# FPGA_SDRAM.net
KiCad netlist of a schematic drawn in Altium Designer
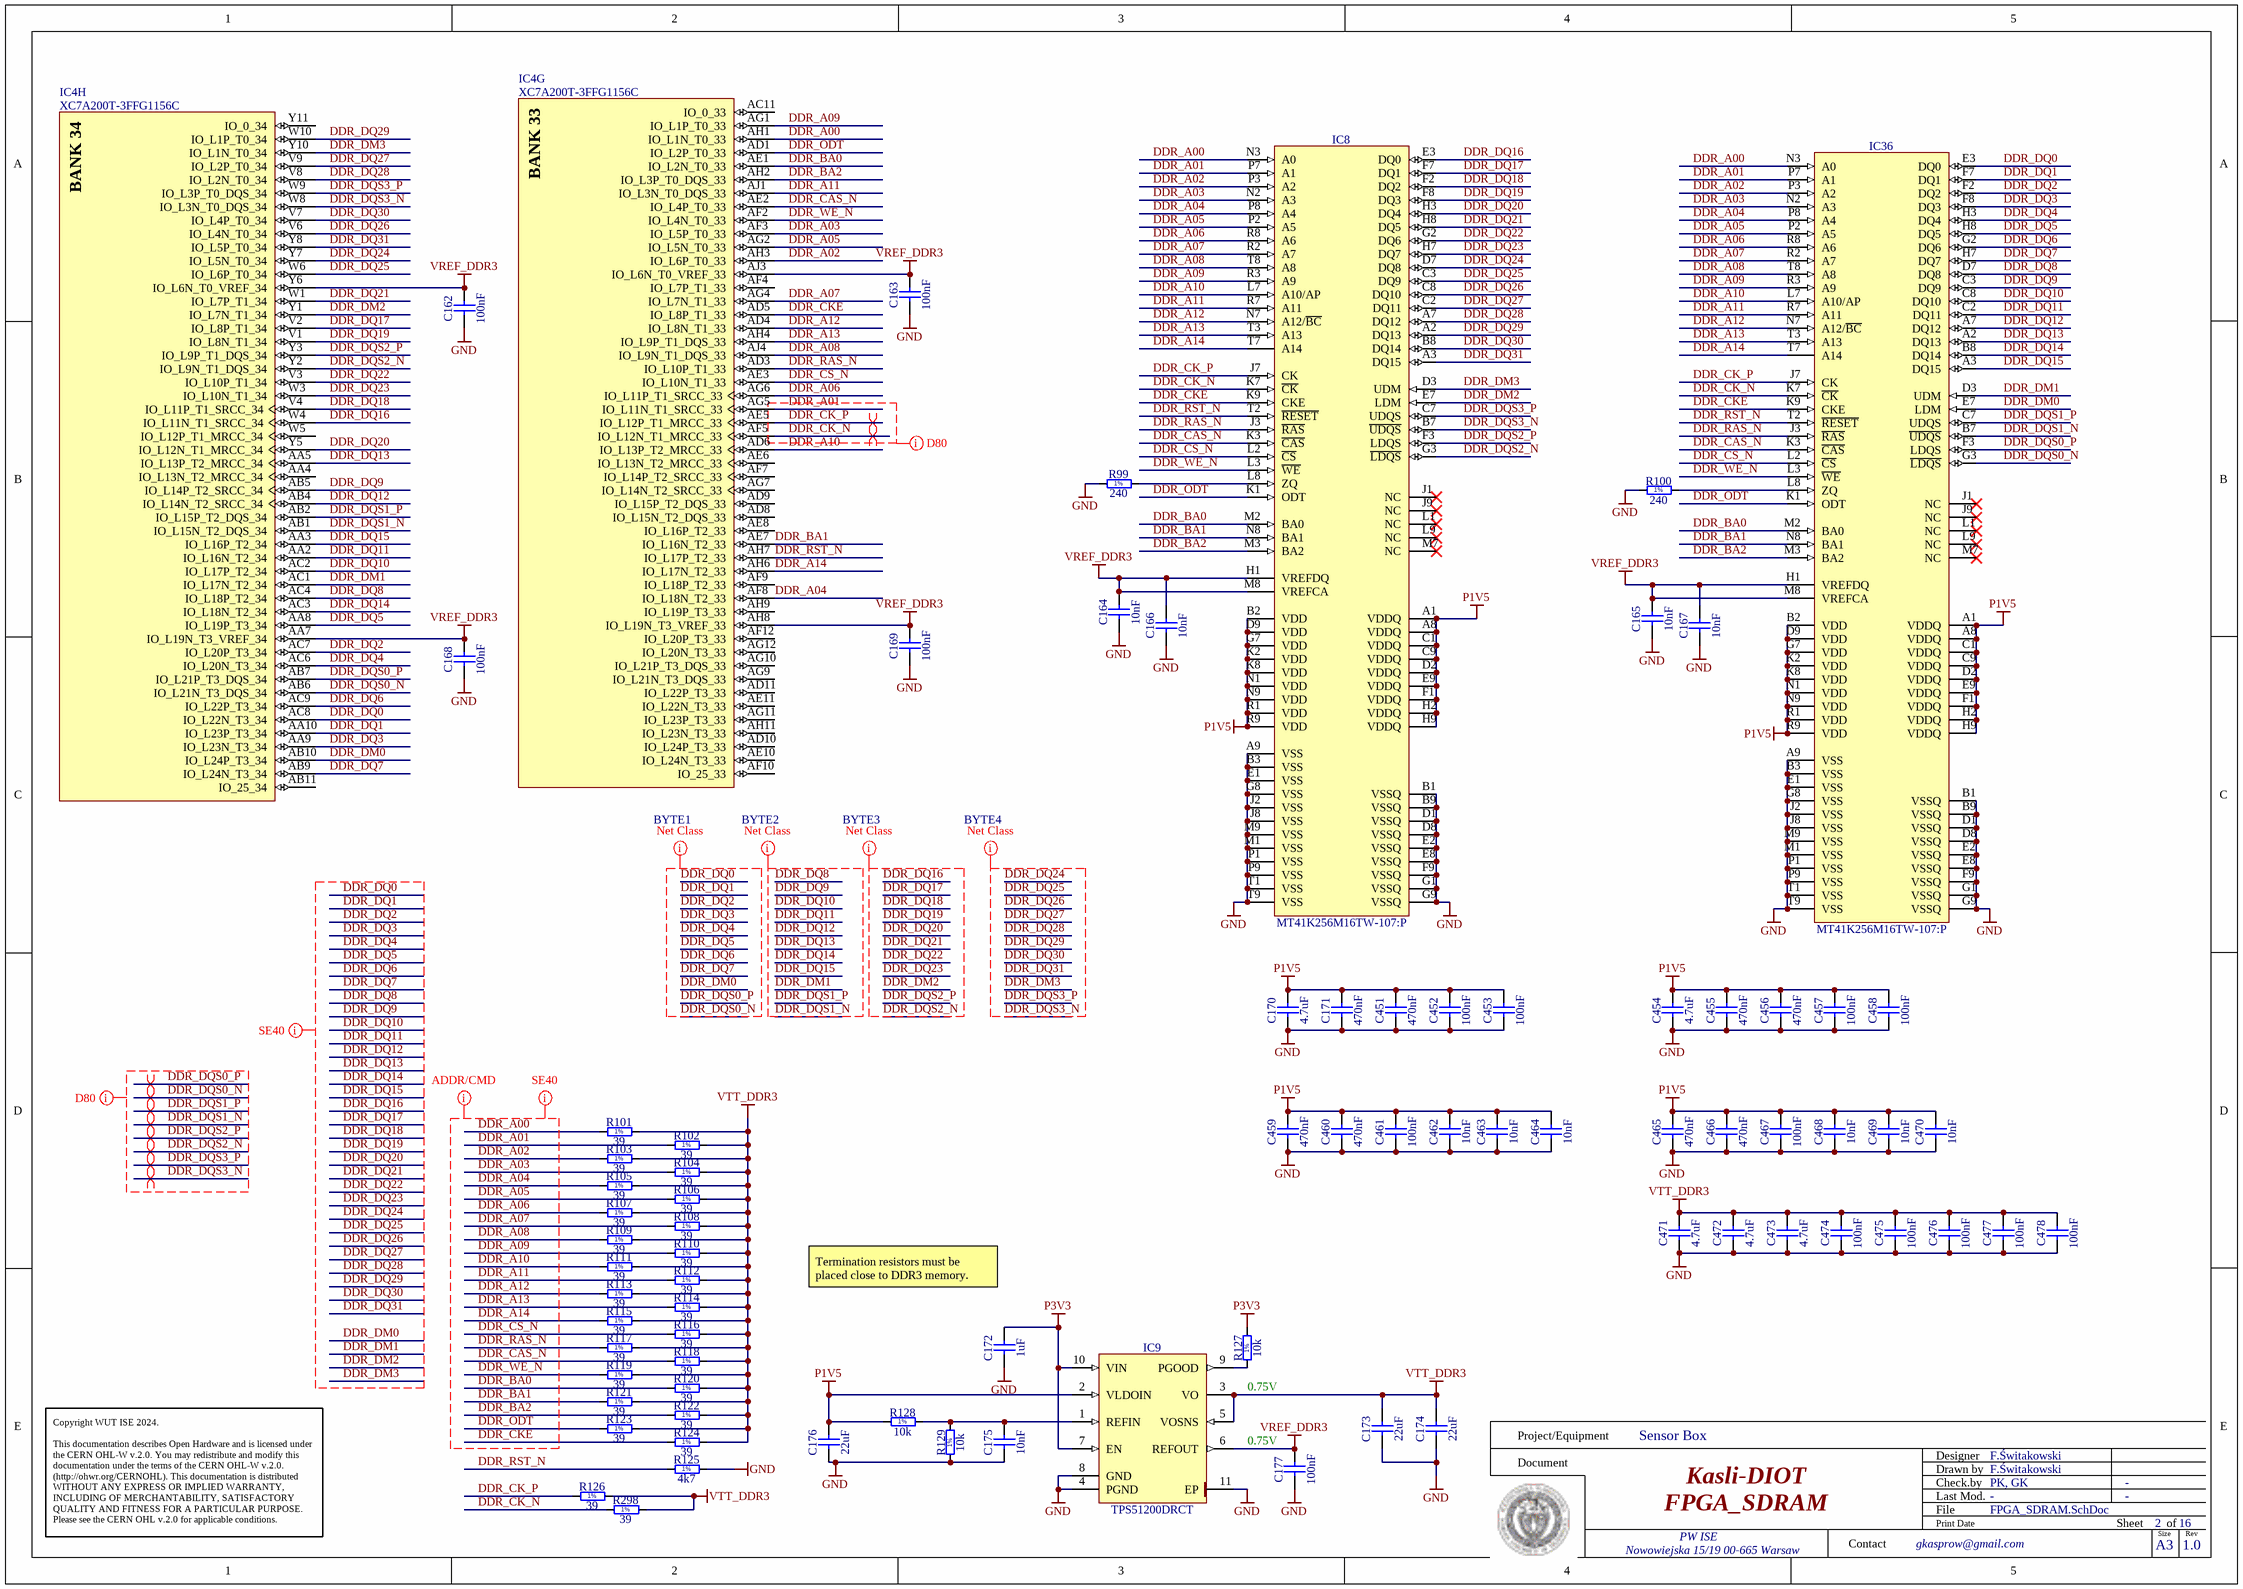
[diagram p0: FPGA_SDRAM.SchDoc]

(export (version "E")
  (design (tool "Eeschema 10.0.6"))
  (components
    (comp (ref "C162")
      (value "100nF")
      (footprint "CAPC1005X55N")
      (description "Non-polarised capacitor")
      (fields
        (field (name "PART NUMBER") "CC0402_100NF_16V_10%_X7R")
        (field (name "VOLTAGE") "16V")
        (field (name "AUTHOR") "CERN DEM JLC")
      )
      (libsource (lib "Capacitors") (part "Capacitor - non polarized"))
    )
    (comp (ref "C163")
      (value "100nF")
      (footprint "CAPC1005X55N")
      (description "Non-polarised capacitor")
      (fields
        (field (name "PART NUMBER") "CC0402_100NF_16V_10%_X7R")
        (field (name "VOLTAGE") "16V")
        (field (name "AUTHOR") "CERN DEM JLC")
      )
      (libsource (lib "Capacitors") (part "Capacitor - non polarized"))
    )
    (comp (ref "C164")
      (value "10nF")
      (footprint "CAPC1005X55N")
      (description "Non-polarised capacitor")
      (fields
        (field (name "PART NUMBER") "CC0402_10NF_16V_10%_X7R")
        (field (name "VOLTAGE") "16V")
        (field (name "AUTHOR") "CERN DEM JLC")
      )
      (libsource (lib "Capacitors") (part "Capacitor - non polarized"))
    )
    (comp (ref "C165")
      (value "10nF")
      (footprint "CAPC1005X55N")
      (description "Non-polarised capacitor")
      (fields
        (field (name "PART NUMBER") "CC0402_10NF_16V_10%_X7R")
        (field (name "VOLTAGE") "16V")
        (field (name "AUTHOR") "CERN DEM JLC")
      )
      (libsource (lib "Capacitors") (part "Capacitor - non polarized"))
    )
    (comp (ref "C166")
      (value "10nF")
      (footprint "CAPC1005X55N")
      (description "Non-polarised capacitor")
      (fields
        (field (name "PART NUMBER") "CC0402_10NF_16V_10%_X7R")
        (field (name "VOLTAGE") "16V")
        (field (name "AUTHOR") "CERN DEM JLC")
      )
      (libsource (lib "Capacitors") (part "Capacitor - non polarized"))
    )
    (comp (ref "C167")
      (value "10nF")
      (footprint "CAPC1005X55N")
      (description "Non-polarised capacitor")
      (fields
        (field (name "PART NUMBER") "CC0402_10NF_16V_10%_X7R")
        (field (name "VOLTAGE") "16V")
        (field (name "AUTHOR") "CERN DEM JLC")
      )
      (libsource (lib "Capacitors") (part "Capacitor - non polarized"))
    )
    (comp (ref "C168")
      (value "100nF")
      (footprint "CAPC1005X55N")
      (description "Non-polarised capacitor")
      (fields
        (field (name "PART NUMBER") "CC0402_100NF_16V_10%_X7R")
        (field (name "VOLTAGE") "16V")
        (field (name "AUTHOR") "CERN DEM JLC")
      )
      (libsource (lib "Capacitors") (part "Capacitor - non polarized"))
    )
    (comp (ref "C169")
      (value "100nF")
      (footprint "CAPC1005X55N")
      (description "Non-polarised capacitor")
      (fields
        (field (name "PART NUMBER") "CC0402_100NF_16V_10%_X7R")
        (field (name "VOLTAGE") "16V")
        (field (name "AUTHOR") "CERN DEM JLC")
      )
      (libsource (lib "Capacitors") (part "Capacitor - non polarized"))
    )
    (comp (ref "C170")
      (value "4.7uF")
      (footprint "CAPC1005X55N")
      (description "Non-polarised capacitor")
      (fields
        (field (name "PART NUMBER") "CC0402_4.7UF_6.3V_20%_X5R")
        (field (name "VOLTAGE") "6.3V")
        (field (name "AUTHOR") "CERN DEM JLC")
      )
      (libsource (lib "Capacitors") (part "Capacitor - non polarized"))
    )
    (comp (ref "C171")
      (value "470nF")
      (footprint "CAPC1005X55N")
      (description "Non-polarised capacitor")
      (fields
        (field (name "PART NUMBER") "CC0402_470NF_16V_10%_X5R")
        (field (name "VOLTAGE") "16V")
        (field (name "AUTHOR") "CERN DEM JLC")
      )
      (libsource (lib "Capacitors") (part "Capacitor - non polarized"))
    )
    (comp (ref "C172")
      (value "1uF")
      (footprint "CAPC1005X55N")
      (description "Non-polarised capacitor")
      (fields
        (field (name "PART NUMBER") "CC0402_1UF_16V_10%_X5R")
        (field (name "VOLTAGE") "16V")
        (field (name "AUTHOR") "CERN DEM JLC")
      )
      (libsource (lib "Capacitors") (part "Capacitor - non polarized"))
    )
    (comp (ref "C173")
      (value "22uF")
      (footprint "CAPC1709X100N")
      (description "Non-polarised capacitor")
      (fields
        (field (name "PART NUMBER") "CC0603_22UF_6.3V_20%_X5R")
        (field (name "VOLTAGE") "6.3V")
        (field (name "AUTHOR") "CERN DEM JLC")
      )
      (libsource (lib "Capacitors") (part "Capacitor - non polarized"))
    )
    (comp (ref "C174")
      (value "22uF")
      (footprint "CAPC1709X100N")
      (description "Non-polarised capacitor")
      (fields
        (field (name "PART NUMBER") "CC0603_22UF_6.3V_20%_X5R")
        (field (name "VOLTAGE") "6.3V")
        (field (name "AUTHOR") "CERN DEM JLC")
      )
      (libsource (lib "Capacitors") (part "Capacitor - non polarized"))
    )
    (comp (ref "C175")
      (value "10nF")
      (footprint "CAPC1005X55N")
      (description "Non-polarised capacitor")
      (fields
        (field (name "PART NUMBER") "CC0402_10NF_16V_10%_X7R")
        (field (name "VOLTAGE") "16V")
        (field (name "AUTHOR") "CERN DEM JLC")
      )
      (libsource (lib "Capacitors") (part "Capacitor - non polarized"))
    )
    (comp (ref "C176")
      (value "22uF")
      (footprint "CAPC1709X100N")
      (description "Non-polarised capacitor")
      (fields
        (field (name "PART NUMBER") "CC0603_22UF_6.3V_20%_X5R")
        (field (name "VOLTAGE") "6.3V")
        (field (name "AUTHOR") "CERN DEM JLC")
      )
      (libsource (lib "Capacitors") (part "Capacitor - non polarized"))
    )
    (comp (ref "C177")
      (value "100nF")
      (footprint "CAPC1005X55N")
      (description "Non-polarised capacitor")
      (fields
        (field (name "PART NUMBER") "CC0402_100NF_16V_10%_X7R")
        (field (name "VOLTAGE") "16V")
        (field (name "AUTHOR") "CERN DEM JLC")
      )
      (libsource (lib "Capacitors") (part "Capacitor - non polarized"))
    )
    (comp (ref "C451")
      (value "470nF")
      (footprint "CAPC1005X55N")
      (description "Non-polarised capacitor")
      (fields
        (field (name "PART NUMBER") "CC0402_470NF_16V_10%_X5R")
        (field (name "VOLTAGE") "16V")
        (field (name "AUTHOR") "CERN DEM JLC")
      )
      (libsource (lib "Capacitors") (part "Capacitor - non polarized"))
    )
    (comp (ref "C452")
      (value "100nF")
      (footprint "CAPC1005X55N")
      (description "Non-polarised capacitor")
      (fields
        (field (name "PART NUMBER") "CC0402_100NF_16V_10%_X7R")
        (field (name "VOLTAGE") "16V")
        (field (name "AUTHOR") "CERN DEM JLC")
      )
      (libsource (lib "Capacitors") (part "Capacitor - non polarized"))
    )
    (comp (ref "C453")
      (value "100nF")
      (footprint "CAPC1005X55N")
      (description "Non-polarised capacitor")
      (fields
        (field (name "PART NUMBER") "CC0402_100NF_16V_10%_X7R")
        (field (name "VOLTAGE") "16V")
        (field (name "AUTHOR") "CERN DEM JLC")
      )
      (libsource (lib "Capacitors") (part "Capacitor - non polarized"))
    )
    (comp (ref "C454")
      (value "4.7uF")
      (footprint "CAPC1005X55N")
      (description "Non-polarised capacitor")
      (fields
        (field (name "PART NUMBER") "CC0402_4.7UF_6.3V_20%_X5R")
        (field (name "VOLTAGE") "6.3V")
        (field (name "AUTHOR") "CERN DEM JLC")
      )
      (libsource (lib "Capacitors") (part "Capacitor - non polarized"))
    )
    (comp (ref "C455")
      (value "470nF")
      (footprint "CAPC1005X55N")
      (description "Non-polarised capacitor")
      (fields
        (field (name "PART NUMBER") "CC0402_470NF_16V_10%_X5R")
        (field (name "VOLTAGE") "16V")
        (field (name "AUTHOR") "CERN DEM JLC")
      )
      (libsource (lib "Capacitors") (part "Capacitor - non polarized"))
    )
    (comp (ref "C456")
      (value "470nF")
      (footprint "CAPC1005X55N")
      (description "Non-polarised capacitor")
      (fields
        (field (name "PART NUMBER") "CC0402_470NF_16V_10%_X5R")
        (field (name "VOLTAGE") "16V")
        (field (name "AUTHOR") "CERN DEM JLC")
      )
      (libsource (lib "Capacitors") (part "Capacitor - non polarized"))
    )
    (comp (ref "C457")
      (value "100nF")
      (footprint "CAPC1005X55N")
      (description "Non-polarised capacitor")
      (fields
        (field (name "PART NUMBER") "CC0402_100NF_16V_10%_X7R")
        (field (name "VOLTAGE") "16V")
        (field (name "AUTHOR") "CERN DEM JLC")
      )
      (libsource (lib "Capacitors") (part "Capacitor - non polarized"))
    )
    (comp (ref "C458")
      (value "100nF")
      (footprint "CAPC1005X55N")
      (description "Non-polarised capacitor")
      (fields
        (field (name "PART NUMBER") "CC0402_100NF_16V_10%_X7R")
        (field (name "VOLTAGE") "16V")
        (field (name "AUTHOR") "CERN DEM JLC")
      )
      (libsource (lib "Capacitors") (part "Capacitor - non polarized"))
    )
    (comp (ref "C459")
      (value "470nF")
      (footprint "CAPC1005X55N")
      (description "Non-polarised capacitor")
      (fields
        (field (name "PART NUMBER") "CC0402_470NF_16V_10%_X5R")
        (field (name "VOLTAGE") "16V")
        (field (name "AUTHOR") "CERN DEM JLC")
      )
      (libsource (lib "Capacitors") (part "Capacitor - non polarized"))
    )
    (comp (ref "C460")
      (value "470nF")
      (footprint "CAPC1005X55N")
      (description "Non-polarised capacitor")
      (fields
        (field (name "PART NUMBER") "CC0402_470NF_16V_10%_X5R")
        (field (name "VOLTAGE") "16V")
        (field (name "AUTHOR") "CERN DEM JLC")
      )
      (libsource (lib "Capacitors") (part "Capacitor - non polarized"))
    )
    (comp (ref "C461")
      (value "100nF")
      (footprint "CAPC1005X55N")
      (description "Non-polarised capacitor")
      (fields
        (field (name "PART NUMBER") "CC0402_100NF_16V_10%_X7R")
        (field (name "VOLTAGE") "16V")
        (field (name "AUTHOR") "CERN DEM JLC")
      )
      (libsource (lib "Capacitors") (part "Capacitor - non polarized"))
    )
    (comp (ref "C462")
      (value "10nF")
      (footprint "CAPC1005X55N")
      (description "Non-polarised capacitor")
      (fields
        (field (name "PART NUMBER") "CC0402_10NF_16V_10%_X7R")
        (field (name "VOLTAGE") "16V")
        (field (name "AUTHOR") "CERN DEM JLC")
      )
      (libsource (lib "Capacitors") (part "Capacitor - non polarized"))
    )
    (comp (ref "C463")
      (value "10nF")
      (footprint "CAPC1005X55N")
      (description "Non-polarised capacitor")
      (fields
        (field (name "PART NUMBER") "CC0402_10NF_16V_10%_X7R")
        (field (name "VOLTAGE") "16V")
        (field (name "AUTHOR") "CERN DEM JLC")
      )
      (libsource (lib "Capacitors") (part "Capacitor - non polarized"))
    )
    (comp (ref "C464")
      (value "10nF")
      (footprint "CAPC1005X55N")
      (description "Non-polarised capacitor")
      (fields
        (field (name "PART NUMBER") "CC0402_10NF_16V_10%_X7R")
        (field (name "VOLTAGE") "16V")
        (field (name "AUTHOR") "CERN DEM JLC")
      )
      (libsource (lib "Capacitors") (part "Capacitor - non polarized"))
    )
    (comp (ref "C465")
      (value "470nF")
      (footprint "CAPC1005X55N")
      (description "Non-polarised capacitor")
      (fields
        (field (name "PART NUMBER") "CC0402_470NF_16V_10%_X5R")
        (field (name "VOLTAGE") "16V")
        (field (name "AUTHOR") "CERN DEM JLC")
      )
      (libsource (lib "Capacitors") (part "Capacitor - non polarized"))
    )
    (comp (ref "C466")
      (value "470nF")
      (footprint "CAPC1005X55N")
      (description "Non-polarised capacitor")
      (fields
        (field (name "PART NUMBER") "CC0402_470NF_16V_10%_X5R")
        (field (name "VOLTAGE") "16V")
        (field (name "AUTHOR") "CERN DEM JLC")
      )
      (libsource (lib "Capacitors") (part "Capacitor - non polarized"))
    )
    (comp (ref "C467")
      (value "100nF")
      (footprint "CAPC1005X55N")
      (description "Non-polarised capacitor")
      (fields
        (field (name "PART NUMBER") "CC0402_100NF_16V_10%_X7R")
        (field (name "VOLTAGE") "16V")
        (field (name "AUTHOR") "CERN DEM JLC")
      )
      (libsource (lib "Capacitors") (part "Capacitor - non polarized"))
    )
    (comp (ref "C468")
      (value "10nF")
      (footprint "CAPC1005X55N")
      (description "Non-polarised capacitor")
      (fields
        (field (name "PART NUMBER") "CC0402_10NF_16V_10%_X7R")
        (field (name "VOLTAGE") "16V")
        (field (name "AUTHOR") "CERN DEM JLC")
      )
      (libsource (lib "Capacitors") (part "Capacitor - non polarized"))
    )
    (comp (ref "C469")
      (value "10nF")
      (footprint "CAPC1005X55N")
      (description "Non-polarised capacitor")
      (fields
        (field (name "PART NUMBER") "CC0402_10NF_16V_10%_X7R")
        (field (name "VOLTAGE") "16V")
        (field (name "AUTHOR") "CERN DEM JLC")
      )
      (libsource (lib "Capacitors") (part "Capacitor - non polarized"))
    )
    (comp (ref "C470")
      (value "10nF")
      (footprint "CAPC1005X55N")
      (description "Non-polarised capacitor")
      (fields
        (field (name "PART NUMBER") "CC0402_10NF_16V_10%_X7R")
        (field (name "VOLTAGE") "16V")
        (field (name "AUTHOR") "CERN DEM JLC")
      )
      (libsource (lib "Capacitors") (part "Capacitor - non polarized"))
    )
    (comp (ref "C471")
      (value "4.7uF")
      (footprint "CAPC1005X55N")
      (description "Non-polarised capacitor")
      (fields
        (field (name "PART NUMBER") "CC0402_4.7UF_6.3V_20%_X5R")
        (field (name "VOLTAGE") "6.3V")
        (field (name "AUTHOR") "CERN DEM JLC")
      )
      (libsource (lib "Capacitors") (part "Capacitor - non polarized"))
    )
    (comp (ref "C472")
      (value "4.7uF")
      (footprint "CAPC1005X55N")
      (description "Non-polarised capacitor")
      (fields
        (field (name "PART NUMBER") "CC0402_4.7UF_6.3V_20%_X5R")
        (field (name "VOLTAGE") "6.3V")
        (field (name "AUTHOR") "CERN DEM JLC")
      )
      (libsource (lib "Capacitors") (part "Capacitor - non polarized"))
    )
    (comp (ref "C473")
      (value "4.7uF")
      (footprint "CAPC1005X55N")
      (description "Non-polarised capacitor")
      (fields
        (field (name "PART NUMBER") "CC0402_4.7UF_6.3V_20%_X5R")
        (field (name "VOLTAGE") "6.3V")
        (field (name "AUTHOR") "CERN DEM JLC")
      )
      (libsource (lib "Capacitors") (part "Capacitor - non polarized"))
    )
    (comp (ref "C474")
      (value "100nF")
      (footprint "CAPC1005X55N")
      (description "Non-polarised capacitor")
      (fields
        (field (name "PART NUMBER") "CC0402_100NF_16V_10%_X7R")
        (field (name "VOLTAGE") "16V")
        (field (name "AUTHOR") "CERN DEM JLC")
      )
      (libsource (lib "Capacitors") (part "Capacitor - non polarized"))
    )
    (comp (ref "C475")
      (value "100nF")
      (footprint "CAPC1005X55N")
      (description "Non-polarised capacitor")
      (fields
        (field (name "PART NUMBER") "CC0402_100NF_16V_10%_X7R")
        (field (name "VOLTAGE") "16V")
        (field (name "AUTHOR") "CERN DEM JLC")
      )
      (libsource (lib "Capacitors") (part "Capacitor - non polarized"))
    )
    (comp (ref "C476")
      (value "100nF")
      (footprint "CAPC1005X55N")
      (description "Non-polarised capacitor")
      (fields
        (field (name "PART NUMBER") "CC0402_100NF_16V_10%_X7R")
        (field (name "VOLTAGE") "16V")
        (field (name "AUTHOR") "CERN DEM JLC")
      )
      (libsource (lib "Capacitors") (part "Capacitor - non polarized"))
    )
    (comp (ref "C477")
      (value "100nF")
      (footprint "CAPC1005X55N")
      (description "Non-polarised capacitor")
      (fields
        (field (name "PART NUMBER") "CC0402_100NF_16V_10%_X7R")
        (field (name "VOLTAGE") "16V")
        (field (name "AUTHOR") "CERN DEM JLC")
      )
      (libsource (lib "Capacitors") (part "Capacitor - non polarized"))
    )
    (comp (ref "C478")
      (value "100nF")
      (footprint "CAPC1005X55N")
      (description "Non-polarised capacitor")
      (fields
        (field (name "PART NUMBER") "CC0402_100NF_16V_10%_X7R")
        (field (name "VOLTAGE") "16V")
        (field (name "AUTHOR") "CERN DEM JLC")
      )
      (libsource (lib "Capacitors") (part "Capacitor - non polarized"))
    )
    (comp (ref "IC4")
      (value "XC7A200T-3FFG1156C")
      (footprint "BGA1156C100P34X34_3500X3500X310")
      (description "Artix-7 FPGA, 500 User I/Os, 16 GTP, 1156-Ball BGA, , Speed Grade 3, Commercial Grade, Pb-Free")
      (fields (field (name "MANUFACTURER") "XILINX") (field (name "AUTHOR") "CERN DEM JLC"))
      (libsource (lib "ICs And Semiconductors") (part "XC7A200T-3FFG1156C"))
    )
    (comp (ref "IC8")
      (value "MT41K256M16TW-107:P")
      (footprint "BGA96C80P9X16_800X1400X120")
      (description "32 Meg x 16 x 8 Banks DDR3L SDRAM")
      (fields (field (name "MANUFACTURER") "MICRON TECHNOLOGY") (field (name "AUTHOR") "CERN DEM MR"))
      (libsource (lib "ICs And Semiconductors") (part "MT41K256M16TW-107{colon}P"))
    )
    (comp (ref "IC9")
      (value "TPS51200DRCT")
      (footprint "TEXAS_DRC (S-PVSON-N10)")
      (description "Sink/Source DDR Termination Regulator")
      (fields (field (name "MANUFACTURER") "TEXAS INSTRUMENTS") (field (name "AUTHOR") "CERN DEM JLC"))
      (libsource (lib "ICs And Semiconductors") (part "TPS51200DRC"))
    )
    (comp (ref "IC36")
      (value "MT41K256M16TW-107:P")
      (footprint "BGA96C80P9X16_800X1400X120")
      (description "32 Meg x 16 x 8 Banks DDR3L SDRAM")
      (fields (field (name "MANUFACTURER") "MICRON TECHNOLOGY") (field (name "AUTHOR") "CERN DEM MR"))
      (libsource (lib "ICs And Semiconductors") (part "MT41K256M16TW-107{colon}P"))
    )
    (comp (ref "R99")
      (value "240")
      (footprint "RESC1005X40N")
      (description "Resistor - 1%")
      (fields
        (field (name "PART NUMBER") "R0402_240R_1%_0.0625W_100PPM")
        (field (name "POWER") "0.0625W")
        (field (name "AUTHOR") "CERN DEM JLC")
      )
      (libsource (lib "Resistors") (part "Resistor - 1%"))
    )
    (comp (ref "R100")
      (value "240")
      (footprint "RESC1005X40N")
      (description "Resistor - 1%")
      (fields
        (field (name "PART NUMBER") "R0402_240R_1%_0.0625W_100PPM")
        (field (name "POWER") "0.0625W")
        (field (name "AUTHOR") "CERN DEM JLC")
      )
      (libsource (lib "Resistors") (part "Resistor - 1%"))
    )
    (comp (ref "R101")
      (value "39")
      (footprint "RESC1005X40N")
      (description "Resistor - 1%")
      (fields
        (field (name "PART NUMBER") "R0402_39R_1%_0.0625W_100PPM")
        (field (name "POWER") "0.0625W")
        (field (name "AUTHOR") "CERN DEM JLC")
      )
      (libsource (lib "Resistors") (part "Resistor - 1%"))
    )
    (comp (ref "R102")
      (value "39")
      (footprint "RESC1005X40N")
      (description "Resistor - 1%")
      (fields
        (field (name "PART NUMBER") "R0402_39R_1%_0.0625W_100PPM")
        (field (name "POWER") "0.0625W")
        (field (name "AUTHOR") "CERN DEM JLC")
      )
      (libsource (lib "Resistors") (part "Resistor - 1%"))
    )
    (comp (ref "R103")
      (value "39")
      (footprint "RESC1005X40N")
      (description "Resistor - 1%")
      (fields
        (field (name "PART NUMBER") "R0402_39R_1%_0.0625W_100PPM")
        (field (name "POWER") "0.0625W")
        (field (name "AUTHOR") "CERN DEM JLC")
      )
      (libsource (lib "Resistors") (part "Resistor - 1%"))
    )
    (comp (ref "R104")
      (value "39")
      (footprint "RESC1005X40N")
      (description "Resistor - 1%")
      (fields
        (field (name "PART NUMBER") "R0402_39R_1%_0.0625W_100PPM")
        (field (name "POWER") "0.0625W")
        (field (name "AUTHOR") "CERN DEM JLC")
      )
      (libsource (lib "Resistors") (part "Resistor - 1%"))
    )
    (comp (ref "R105")
      (value "39")
      (footprint "RESC1005X40N")
      (description "Resistor - 1%")
      (fields
        (field (name "PART NUMBER") "R0402_39R_1%_0.0625W_100PPM")
        (field (name "POWER") "0.0625W")
        (field (name "AUTHOR") "CERN DEM JLC")
      )
      (libsource (lib "Resistors") (part "Resistor - 1%"))
    )
    (comp (ref "R106")
      (value "39")
      (footprint "RESC1005X40N")
      (description "Resistor - 1%")
      (fields
        (field (name "PART NUMBER") "R0402_39R_1%_0.0625W_100PPM")
        (field (name "POWER") "0.0625W")
        (field (name "AUTHOR") "CERN DEM JLC")
      )
      (libsource (lib "Resistors") (part "Resistor - 1%"))
    )
    (comp (ref "R107")
      (value "39")
      (footprint "RESC1005X40N")
      (description "Resistor - 1%")
      (fields
        (field (name "PART NUMBER") "R0402_39R_1%_0.0625W_100PPM")
        (field (name "POWER") "0.0625W")
        (field (name "AUTHOR") "CERN DEM JLC")
      )
      (libsource (lib "Resistors") (part "Resistor - 1%"))
    )
    (comp (ref "R108")
      (value "39")
      (footprint "RESC1005X40N")
      (description "Resistor - 1%")
      (fields
        (field (name "PART NUMBER") "R0402_39R_1%_0.0625W_100PPM")
        (field (name "POWER") "0.0625W")
        (field (name "AUTHOR") "CERN DEM JLC")
      )
      (libsource (lib "Resistors") (part "Resistor - 1%"))
    )
    (comp (ref "R109")
      (value "39")
      (footprint "RESC1005X40N")
      (description "Resistor - 1%")
      (fields
        (field (name "PART NUMBER") "R0402_39R_1%_0.0625W_100PPM")
        (field (name "POWER") "0.0625W")
        (field (name "AUTHOR") "CERN DEM JLC")
      )
      (libsource (lib "Resistors") (part "Resistor - 1%"))
    )
    (comp (ref "R110")
      (value "39")
      (footprint "RESC1005X40N")
      (description "Resistor - 1%")
      (fields
        (field (name "PART NUMBER") "R0402_39R_1%_0.0625W_100PPM")
        (field (name "POWER") "0.0625W")
        (field (name "AUTHOR") "CERN DEM JLC")
      )
      (libsource (lib "Resistors") (part "Resistor - 1%"))
    )
    (comp (ref "R111")
      (value "39")
      (footprint "RESC1005X40N")
      (description "Resistor - 1%")
      (fields
        (field (name "PART NUMBER") "R0402_39R_1%_0.0625W_100PPM")
        (field (name "POWER") "0.0625W")
        (field (name "AUTHOR") "CERN DEM JLC")
      )
      (libsource (lib "Resistors") (part "Resistor - 1%"))
    )
    (comp (ref "R112")
      (value "39")
      (footprint "RESC1005X40N")
      (description "Resistor - 1%")
      (fields
        (field (name "PART NUMBER") "R0402_39R_1%_0.0625W_100PPM")
        (field (name "POWER") "0.0625W")
        (field (name "AUTHOR") "CERN DEM JLC")
      )
      (libsource (lib "Resistors") (part "Resistor - 1%"))
    )
    (comp (ref "R113")
      (value "39")
      (footprint "RESC1005X40N")
      (description "Resistor - 1%")
      (fields
        (field (name "PART NUMBER") "R0402_39R_1%_0.0625W_100PPM")
        (field (name "POWER") "0.0625W")
        (field (name "AUTHOR") "CERN DEM JLC")
      )
      (libsource (lib "Resistors") (part "Resistor - 1%"))
    )
    (comp (ref "R114")
      (value "39")
      (footprint "RESC1005X40N")
      (description "Resistor - 1%")
      (fields
        (field (name "PART NUMBER") "R0402_39R_1%_0.0625W_100PPM")
        (field (name "POWER") "0.0625W")
        (field (name "AUTHOR") "CERN DEM JLC")
      )
      (libsource (lib "Resistors") (part "Resistor - 1%"))
    )
    (comp (ref "R115")
      (value "39")
      (footprint "RESC1005X40N")
      (description "Resistor - 1%")
      (fields
        (field (name "PART NUMBER") "R0402_39R_1%_0.0625W_100PPM")
        (field (name "POWER") "0.0625W")
        (field (name "AUTHOR") "CERN DEM JLC")
      )
      (libsource (lib "Resistors") (part "Resistor - 1%"))
    )
    (comp (ref "R116")
      (value "39")
      (footprint "RESC1005X40N")
      (description "Resistor - 1%")
      (fields
        (field (name "PART NUMBER") "R0402_39R_1%_0.0625W_100PPM")
        (field (name "POWER") "0.0625W")
        (field (name "AUTHOR") "CERN DEM JLC")
      )
      (libsource (lib "Resistors") (part "Resistor - 1%"))
    )
    (comp (ref "R117")
      (value "39")
      (footprint "RESC1005X40N")
      (description "Resistor - 1%")
      (fields
        (field (name "PART NUMBER") "R0402_39R_1%_0.0625W_100PPM")
        (field (name "POWER") "0.0625W")
        (field (name "AUTHOR") "CERN DEM JLC")
      )
      (libsource (lib "Resistors") (part "Resistor - 1%"))
    )
    (comp (ref "R118")
      (value "39")
      (footprint "RESC1005X40N")
      (description "Resistor - 1%")
      (fields
        (field (name "PART NUMBER") "R0402_39R_1%_0.0625W_100PPM")
        (field (name "POWER") "0.0625W")
        (field (name "AUTHOR") "CERN DEM JLC")
      )
      (libsource (lib "Resistors") (part "Resistor - 1%"))
    )
    (comp (ref "R119")
      (value "39")
      (footprint "RESC1005X40N")
      (description "Resistor - 1%")
      (fields
        (field (name "PART NUMBER") "R0402_39R_1%_0.0625W_100PPM")
        (field (name "POWER") "0.0625W")
        (field (name "AUTHOR") "CERN DEM JLC")
      )
      (libsource (lib "Resistors") (part "Resistor - 1%"))
    )
    (comp (ref "R120")
      (value "39")
      (footprint "RESC1005X40N")
      (description "Resistor - 1%")
      (fields
        (field (name "PART NUMBER") "R0402_39R_1%_0.0625W_100PPM")
        (field (name "POWER") "0.0625W")
        (field (name "AUTHOR") "CERN DEM JLC")
      )
      (libsource (lib "Resistors") (part "Resistor - 1%"))
    )
    (comp (ref "R121")
      (value "39")
      (footprint "RESC1005X40N")
      (description "Resistor - 1%")
      (fields
        (field (name "PART NUMBER") "R0402_39R_1%_0.0625W_100PPM")
        (field (name "POWER") "0.0625W")
        (field (name "AUTHOR") "CERN DEM JLC")
      )
      (libsource (lib "Resistors") (part "Resistor - 1%"))
    )
    (comp (ref "R122")
      (value "39")
      (footprint "RESC1005X40N")
      (description "Resistor - 1%")
      (fields
        (field (name "PART NUMBER") "R0402_39R_1%_0.0625W_100PPM")
        (field (name "POWER") "0.0625W")
        (field (name "AUTHOR") "CERN DEM JLC")
      )
      (libsource (lib "Resistors") (part "Resistor - 1%"))
    )
    (comp (ref "R123")
      (value "39")
      (footprint "RESC1005X40N")
      (description "Resistor - 1%")
      (fields
        (field (name "PART NUMBER") "R0402_39R_1%_0.0625W_100PPM")
        (field (name "POWER") "0.0625W")
        (field (name "AUTHOR") "CERN DEM JLC")
      )
      (libsource (lib "Resistors") (part "Resistor - 1%"))
    )
    (comp (ref "R124")
      (value "39")
      (footprint "RESC1005X40N")
      (description "Resistor - 1%")
      (fields
        (field (name "PART NUMBER") "R0402_39R_1%_0.0625W_100PPM")
        (field (name "POWER") "0.0625W")
        (field (name "AUTHOR") "CERN DEM JLC")
      )
      (libsource (lib "Resistors") (part "Resistor - 1%"))
    )
    (comp (ref "R125")
      (value "4k7")
      (footprint "RESC1005X40N")
      (description "Resistor - 1%")
      (fields
        (field (name "PART NUMBER") "R0402_4K7_1%_0.0625W_100PPM")
        (field (name "POWER") "0.0625W")
        (field (name "AUTHOR") "CERN DEM JLC")
      )
      (libsource (lib "Resistors") (part "Resistor - 1%"))
    )
    (comp (ref "R126")
      (value "39")
      (footprint "RESC1005X40N")
      (description "Resistor - 1%")
      (fields
        (field (name "PART NUMBER") "R0402_39R_1%_0.0625W_100PPM")
        (field (name "POWER") "0.0625W")
        (field (name "AUTHOR") "CERN DEM JLC")
      )
      (libsource (lib "Resistors") (part "Resistor - 1%"))
    )
    (comp (ref "R127")
      (value "10k")
      (footprint "RESC1005X40N")
      (description "Resistor - 1%")
      (fields
        (field (name "PART NUMBER") "R0402_10K_1%_0.0625W_100PPM")
        (field (name "POWER") "0.0625W")
        (field (name "AUTHOR") "CERN DEM JLC")
      )
      (libsource (lib "Resistors") (part "Resistor - 1%"))
    )
    (comp (ref "R128")
      (value "10k")
      (footprint "RESC1005X40N")
      (description "Resistor - 1%")
      (fields
        (field (name "PART NUMBER") "R0402_10K_1%_0.0625W_100PPM")
        (field (name "POWER") "0.0625W")
        (field (name "AUTHOR") "CERN DEM JLC")
      )
      (libsource (lib "Resistors") (part "Resistor - 1%"))
    )
    (comp (ref "R129")
      (value "10k")
      (footprint "RESC1005X40N")
      (description "Resistor - 1%")
      (fields
        (field (name "PART NUMBER") "R0402_10K_1%_0.0625W_100PPM")
        (field (name "POWER") "0.0625W")
        (field (name "AUTHOR") "CERN DEM JLC")
      )
      (libsource (lib "Resistors") (part "Resistor - 1%"))
    )
    (comp (ref "R298")
      (value "39")
      (footprint "RESC1005X40N")
      (description "Resistor - 1%")
      (fields
        (field (name "PART NUMBER") "R0402_39R_1%_0.0625W_100PPM")
        (field (name "POWER") "0.0625W")
        (field (name "AUTHOR") "CERN DEM JLC")
      )
      (libsource (lib "Resistors") (part "Resistor - 1%"))
    )
  )
  (nets
    (net (code "1") (name "/DDR_A00") (class "Default")
      (node (ref "IC36") (pin "N3") (pinfunction "A0_N3") (pintype "input"))
      (node (ref "IC4") (pin "AH1") (pinfunction "IO_L1N_T0_33_AH1") (pintype "bidirectional"))
      (node (ref "IC8") (pin "N3") (pinfunction "A0_N3") (pintype "input"))
      (node (ref "R101") (pin "1") (pinfunction "1_1") (pintype "passive"))
    )
    (net (code "2") (name "/DDR_A01") (class "Default")
      (node (ref "IC36") (pin "P7") (pinfunction "A1_P7") (pintype "input"))
      (node (ref "IC4") (pin "AG5") (pinfunction "IO_L11N_T1_SRCC_33_AG5") (pintype "bidirectional"))
      (node (ref "IC8") (pin "P7") (pinfunction "A1_P7") (pintype "input"))
      (node (ref "R102") (pin "1") (pinfunction "1_1") (pintype "passive"))
    )
    (net (code "3") (name "/DDR_A02") (class "Default")
      (node (ref "IC36") (pin "P3") (pinfunction "A2_P3") (pintype "input"))
      (node (ref "IC4") (pin "AH3") (pinfunction "IO_L6P_T0_33_AH3") (pintype "bidirectional"))
      (node (ref "IC8") (pin "P3") (pinfunction "A2_P3") (pintype "input"))
      (node (ref "R103") (pin "1") (pinfunction "1_1") (pintype "passive"))
    )
    (net (code "4") (name "/DDR_A03") (class "Default")
      (node (ref "IC36") (pin "N2") (pinfunction "A3_N2") (pintype "input"))
      (node (ref "IC4") (pin "AF3") (pinfunction "IO_L5P_T0_33_AF3") (pintype "bidirectional"))
      (node (ref "IC8") (pin "N2") (pinfunction "A3_N2") (pintype "input"))
      (node (ref "R104") (pin "1") (pinfunction "1_1") (pintype "passive"))
    )
    (net (code "5") (name "/DDR_A04") (class "Default")
      (node (ref "IC36") (pin "P8") (pinfunction "A4_P8") (pintype "input"))
      (node (ref "IC4") (pin "AF8") (pinfunction "IO_L18N_T2_33_AF8") (pintype "bidirectional"))
      (node (ref "IC8") (pin "P8") (pinfunction "A4_P8") (pintype "input"))
      (node (ref "R105") (pin "1") (pinfunction "1_1") (pintype "passive"))
    )
    (net (code "6") (name "/DDR_A05") (class "Default")
      (node (ref "IC36") (pin "P2") (pinfunction "A5_P2") (pintype "input"))
      (node (ref "IC4") (pin "AG2") (pinfunction "IO_L5N_T0_33_AG2") (pintype "bidirectional"))
      (node (ref "IC8") (pin "P2") (pinfunction "A5_P2") (pintype "input"))
      (node (ref "R106") (pin "1") (pinfunction "1_1") (pintype "passive"))
    )
    (net (code "7") (name "/DDR_A06") (class "Default")
      (node (ref "IC36") (pin "R8") (pinfunction "A6_R8") (pintype "input"))
      (node (ref "IC4") (pin "AG6") (pinfunction "IO_L11P_T1_SRCC_33_AG6") (pintype "bidirectional"))
      (node (ref "IC8") (pin "R8") (pinfunction "A6_R8") (pintype "input"))
      (node (ref "R107") (pin "1") (pinfunction "1_1") (pintype "passive"))
    )
    (net (code "8") (name "/DDR_A07") (class "Default")
      (node (ref "IC36") (pin "R2") (pinfunction "A7_R2") (pintype "input"))
      (node (ref "IC4") (pin "AG4") (pinfunction "IO_L7N_T1_33_AG4") (pintype "bidirectional"))
      (node (ref "IC8") (pin "R2") (pinfunction "A7_R2") (pintype "input"))
      (node (ref "R108") (pin "1") (pinfunction "1_1") (pintype "passive"))
    )
    (net (code "9") (name "/DDR_A08") (class "Default")
      (node (ref "IC36") (pin "T8") (pinfunction "A8_T8") (pintype "input"))
      (node (ref "IC4") (pin "AJ4") (pinfunction "IO_L9N_T1_DQS_33_AJ4") (pintype "bidirectional"))
      (node (ref "IC8") (pin "T8") (pinfunction "A8_T8") (pintype "input"))
      (node (ref "R109") (pin "1") (pinfunction "1_1") (pintype "passive"))
    )
    (net (code "10") (name "/DDR_A09") (class "Default")
      (node (ref "IC36") (pin "R3") (pinfunction "A9_R3") (pintype "input"))
      (node (ref "IC4") (pin "AG1") (pinfunction "IO_L1P_T0_33_AG1") (pintype "bidirectional"))
      (node (ref "IC8") (pin "R3") (pinfunction "A9_R3") (pintype "input"))
      (node (ref "R110") (pin "1") (pinfunction "1_1") (pintype "passive"))
    )
    (net (code "11") (name "/DDR_A10") (class "Default")
      (node (ref "IC36") (pin "L7") (pinfunction "A10/AP_L7") (pintype "input"))
      (node (ref "IC4") (pin "AD6") (pinfunction "IO_L13P_T2_MRCC_33_AD6") (pintype "bidirectional"))
      (node (ref "IC8") (pin "L7") (pinfunction "A10/AP_L7") (pintype "input"))
      (node (ref "R111") (pin "1") (pinfunction "1_1") (pintype "passive"))
    )
    (net (code "12") (name "/DDR_A11") (class "Default")
      (node (ref "IC36") (pin "R7") (pinfunction "A11_R7") (pintype "input"))
      (node (ref "IC4") (pin "AJ1") (pinfunction "IO_L3N_T0_DQS_33_AJ1") (pintype "bidirectional"))
      (node (ref "IC8") (pin "R7") (pinfunction "A11_R7") (pintype "input"))
      (node (ref "R112") (pin "1") (pinfunction "1_1") (pintype "passive"))
    )
    (net (code "13") (name "/DDR_A12") (class "Default")
      (node (ref "IC36") (pin "N7") (pinfunction "A12/~{BC}_N7") (pintype "input"))
      (node (ref "IC4") (pin "AD4") (pinfunction "IO_L8N_T1_33_AD4") (pintype "bidirectional"))
      (node (ref "IC8") (pin "N7") (pinfunction "A12/~{BC}_N7") (pintype "input"))
      (node (ref "R113") (pin "1") (pinfunction "1_1") (pintype "passive"))
    )
    (net (code "14") (name "/DDR_A13") (class "Default")
      (node (ref "IC36") (pin "T3") (pinfunction "A13_T3") (pintype "input"))
      (node (ref "IC4") (pin "AH4") (pinfunction "IO_L9P_T1_DQS_33_AH4") (pintype "bidirectional"))
      (node (ref "IC8") (pin "T3") (pinfunction "A13_T3") (pintype "input"))
      (node (ref "R114") (pin "1") (pinfunction "1_1") (pintype "passive"))
    )
    (net (code "15") (name "/DDR_A14") (class "Default")
      (node (ref "IC36") (pin "T7") (pinfunction "A14_T7") (pintype "passive"))
      (node (ref "IC4") (pin "AH6") (pinfunction "IO_L17N_T2_33_AH6") (pintype "bidirectional"))
      (node (ref "IC8") (pin "T7") (pinfunction "A14_T7") (pintype "passive"))
      (node (ref "R115") (pin "1") (pinfunction "1_1") (pintype "passive"))
    )
    (net (code "16") (name "/DDR_BA0") (class "Default")
      (node (ref "IC36") (pin "M2") (pinfunction "BA0_M2") (pintype "input"))
      (node (ref "IC4") (pin "AE1") (pinfunction "IO_L2N_T0_33_AE1") (pintype "bidirectional"))
      (node (ref "IC8") (pin "M2") (pinfunction "BA0_M2") (pintype "input"))
      (node (ref "R120") (pin "1") (pinfunction "1_1") (pintype "passive"))
    )
    (net (code "17") (name "/DDR_BA1") (class "Default")
      (node (ref "IC36") (pin "N8") (pinfunction "BA1_N8") (pintype "input"))
      (node (ref "IC4") (pin "AE7") (pinfunction "IO_L16N_T2_33_AE7") (pintype "bidirectional"))
      (node (ref "IC8") (pin "N8") (pinfunction "BA1_N8") (pintype "input"))
      (node (ref "R121") (pin "1") (pinfunction "1_1") (pintype "passive"))
    )
    (net (code "18") (name "/DDR_BA2") (class "Default")
      (node (ref "IC36") (pin "M3") (pinfunction "BA2_M3") (pintype "input"))
      (node (ref "IC4") (pin "AH2") (pinfunction "IO_L3P_T0_DQS_33_AH2") (pintype "bidirectional"))
      (node (ref "IC8") (pin "M3") (pinfunction "BA2_M3") (pintype "input"))
      (node (ref "R122") (pin "1") (pinfunction "1_1") (pintype "passive"))
    )
    (net (code "19") (name "/DDR_CAS_N") (class "Default")
      (node (ref "IC36") (pin "K3") (pinfunction "~{CAS}_K3") (pintype "input"))
      (node (ref "IC4") (pin "AE2") (pinfunction "IO_L4P_T0_33_AE2") (pintype "bidirectional"))
      (node (ref "IC8") (pin "K3") (pinfunction "~{CAS}_K3") (pintype "input"))
      (node (ref "R118") (pin "1") (pinfunction "1_1") (pintype "passive"))
    )
    (net (code "20") (name "/DDR_CKE") (class "Default")
      (node (ref "IC36") (pin "K9") (pinfunction "CKE_K9") (pintype "input"))
      (node (ref "IC4") (pin "AD5") (pinfunction "IO_L8P_T1_33_AD5") (pintype "bidirectional"))
      (node (ref "IC8") (pin "K9") (pinfunction "CKE_K9") (pintype "input"))
      (node (ref "R124") (pin "1") (pinfunction "1_1") (pintype "passive"))
    )
    (net (code "21") (name "/DDR_CK_N") (class "Default")
      (node (ref "IC36") (pin "K7") (pinfunction "~{CK}_K7") (pintype "input"))
      (node (ref "IC4") (pin "AF5") (pinfunction "IO_L12N_T1_MRCC_33_AF5") (pintype "bidirectional"))
      (node (ref "IC8") (pin "K7") (pinfunction "~{CK}_K7") (pintype "input"))
      (node (ref "R298") (pin "1") (pinfunction "1_1") (pintype "passive"))
    )
    (net (code "22") (name "/DDR_CK_P") (class "Default")
      (node (ref "IC36") (pin "J7") (pinfunction "CK_J7") (pintype "input"))
      (node (ref "IC4") (pin "AE5") (pinfunction "IO_L12P_T1_MRCC_33_AE5") (pintype "bidirectional"))
      (node (ref "IC8") (pin "J7") (pinfunction "CK_J7") (pintype "input"))
      (node (ref "R126") (pin "1") (pinfunction "1_1") (pintype "passive"))
    )
    (net (code "23") (name "/DDR_CS_N") (class "Default")
      (node (ref "IC36") (pin "L2") (pinfunction "~{CS}_L2") (pintype "input"))
      (node (ref "IC4") (pin "AE3") (pinfunction "IO_L10N_T1_33_AE3") (pintype "bidirectional"))
      (node (ref "IC8") (pin "L2") (pinfunction "~{CS}_L2") (pintype "input"))
      (node (ref "R116") (pin "1") (pinfunction "1_1") (pintype "passive"))
    )
    (net (code "24") (name "/DDR_DM0") (class "Default")
      (node (ref "IC36") (pin "E7") (pinfunction "LDM_E7") (pintype "input"))
      (node (ref "IC4") (pin "AB10") (pinfunction "IO_L24P_T3_34_AB10") (pintype "bidirectional"))
    )
    (net (code "25") (name "/DDR_DM1") (class "Default")
      (node (ref "IC36") (pin "D3") (pinfunction "UDM_D3") (pintype "input"))
      (node (ref "IC4") (pin "AC1") (pinfunction "IO_L17N_T2_34_AC1") (pintype "bidirectional"))
    )
    (net (code "26") (name "/DDR_DM2") (class "Default")
      (node (ref "IC4") (pin "Y1") (pinfunction "IO_L7N_T1_34_Y1") (pintype "bidirectional"))
      (node (ref "IC8") (pin "E7") (pinfunction "LDM_E7") (pintype "input"))
    )
    (net (code "27") (name "/DDR_DM3") (class "Default")
      (node (ref "IC4") (pin "Y10") (pinfunction "IO_L1N_T0_34_Y10") (pintype "bidirectional"))
      (node (ref "IC8") (pin "D3") (pinfunction "UDM_D3") (pintype "input"))
    )
    (net (code "28") (name "/DDR_DQ0") (class "Default")
      (node (ref "IC36") (pin "E3") (pinfunction "DQ0_E3") (pintype "bidirectional"))
      (node (ref "IC4") (pin "AC8") (pinfunction "IO_L22N_T3_34_AC8") (pintype "bidirectional"))
    )
    (net (code "29") (name "/DDR_DQ1") (class "Default")
      (node (ref "IC36") (pin "F7") (pinfunction "DQ1_F7") (pintype "bidirectional"))
      (node (ref "IC4") (pin "AA10") (pinfunction "IO_L23P_T3_34_AA10") (pintype "bidirectional"))
    )
    (net (code "30") (name "/DDR_DQ2") (class "Default")
      (node (ref "IC36") (pin "F2") (pinfunction "DQ2_F2") (pintype "bidirectional"))
      (node (ref "IC4") (pin "AC7") (pinfunction "IO_L20P_T3_34_AC7") (pintype "bidirectional"))
    )
    (net (code "31") (name "/DDR_DQ3") (class "Default")
      (node (ref "IC36") (pin "F8") (pinfunction "DQ3_F8") (pintype "bidirectional"))
      (node (ref "IC4") (pin "AA9") (pinfunction "IO_L23N_T3_34_AA9") (pintype "bidirectional"))
    )
    (net (code "32") (name "/DDR_DQ4") (class "Default")
      (node (ref "IC36") (pin "H3") (pinfunction "DQ4_H3") (pintype "bidirectional"))
      (node (ref "IC4") (pin "AC6") (pinfunction "IO_L20N_T3_34_AC6") (pintype "bidirectional"))
    )
    (net (code "33") (name "/DDR_DQ5") (class "Default")
      (node (ref "IC36") (pin "H8") (pinfunction "DQ5_H8") (pintype "bidirectional"))
      (node (ref "IC4") (pin "AA8") (pinfunction "IO_L19P_T3_34_AA8") (pintype "bidirectional"))
    )
    (net (code "34") (name "/DDR_DQ6") (class "Default")
      (node (ref "IC36") (pin "G2") (pinfunction "DQ6_G2") (pintype "bidirectional"))
      (node (ref "IC4") (pin "AC9") (pinfunction "IO_L22P_T3_34_AC9") (pintype "bidirectional"))
    )
    (net (code "35") (name "/DDR_DQ7") (class "Default")
      (node (ref "IC36") (pin "H7") (pinfunction "DQ7_H7") (pintype "bidirectional"))
      (node (ref "IC4") (pin "AB9") (pinfunction "IO_L24N_T3_34_AB9") (pintype "bidirectional"))
    )
    (net (code "36") (name "/DDR_DQ8") (class "Default")
      (node (ref "IC36") (pin "D7") (pinfunction "DQ8_D7") (pintype "bidirectional"))
      (node (ref "IC4") (pin "AC4") (pinfunction "IO_L18P_T2_34_AC4") (pintype "bidirectional"))
    )
    (net (code "37") (name "/DDR_DQ9") (class "Default")
      (node (ref "IC36") (pin "C3") (pinfunction "DQ9_C3") (pintype "bidirectional"))
      (node (ref "IC4") (pin "AB5") (pinfunction "IO_L14P_T2_SRCC_34_AB5") (pintype "bidirectional"))
    )
    (net (code "38") (name "/DDR_DQ10") (class "Default")
      (node (ref "IC36") (pin "C8") (pinfunction "DQ10_C8") (pintype "bidirectional"))
      (node (ref "IC4") (pin "AC2") (pinfunction "IO_L17P_T2_34_AC2") (pintype "bidirectional"))
    )
    (net (code "39") (name "/DDR_DQ11") (class "Default")
      (node (ref "IC36") (pin "C2") (pinfunction "DQ11_C2") (pintype "bidirectional"))
      (node (ref "IC4") (pin "AA2") (pinfunction "IO_L16N_T2_34_AA2") (pintype "bidirectional"))
    )
    (net (code "40") (name "/DDR_DQ12") (class "Default")
      (node (ref "IC36") (pin "A7") (pinfunction "DQ12_A7") (pintype "bidirectional"))
      (node (ref "IC4") (pin "AB4") (pinfunction "IO_L14N_T2_SRCC_34_AB4") (pintype "bidirectional"))
    )
    (net (code "41") (name "/DDR_DQ13") (class "Default")
      (node (ref "IC36") (pin "A2") (pinfunction "DQ13_A2") (pintype "bidirectional"))
      (node (ref "IC4") (pin "AA5") (pinfunction "IO_L13P_T2_MRCC_34_AA5") (pintype "bidirectional"))
    )
    (net (code "42") (name "/DDR_DQ14") (class "Default")
      (node (ref "IC36") (pin "B8") (pinfunction "DQ14_B8") (pintype "bidirectional"))
      (node (ref "IC4") (pin "AC3") (pinfunction "IO_L18N_T2_34_AC3") (pintype "bidirectional"))
    )
    (net (code "43") (name "/DDR_DQ15") (class "Default")
      (node (ref "IC36") (pin "A3") (pinfunction "DQ15_A3") (pintype "bidirectional"))
      (node (ref "IC4") (pin "AA3") (pinfunction "IO_L16P_T2_34_AA3") (pintype "bidirectional"))
    )
    (net (code "44") (name "/DDR_DQ16") (class "Default")
      (node (ref "IC4") (pin "W4") (pinfunction "IO_L11N_T1_SRCC_34_W4") (pintype "bidirectional"))
      (node (ref "IC8") (pin "E3") (pinfunction "DQ0_E3") (pintype "bidirectional"))
    )
    (net (code "45") (name "/DDR_DQ17") (class "Default")
      (node (ref "IC4") (pin "V2") (pinfunction "IO_L8P_T1_34_V2") (pintype "bidirectional"))
      (node (ref "IC8") (pin "F7") (pinfunction "DQ1_F7") (pintype "bidirectional"))
    )
    (net (code "46") (name "/DDR_DQ18") (class "Default")
      (node (ref "IC4") (pin "V4") (pinfunction "IO_L11P_T1_SRCC_34_V4") (pintype "bidirectional"))
      (node (ref "IC8") (pin "F2") (pinfunction "DQ2_F2") (pintype "bidirectional"))
    )
    (net (code "47") (name "/DDR_DQ19") (class "Default")
      (node (ref "IC4") (pin "V1") (pinfunction "IO_L8N_T1_34_V1") (pintype "bidirectional"))
      (node (ref "IC8") (pin "F8") (pinfunction "DQ3_F8") (pintype "bidirectional"))
    )
    (net (code "48") (name "/DDR_DQ20") (class "Default")
      (node (ref "IC4") (pin "Y5") (pinfunction "IO_L12N_T1_MRCC_34_Y5") (pintype "bidirectional"))
      (node (ref "IC8") (pin "H3") (pinfunction "DQ4_H3") (pintype "bidirectional"))
    )
    (net (code "49") (name "/DDR_DQ21") (class "Default")
      (node (ref "IC4") (pin "W1") (pinfunction "IO_L7P_T1_34_W1") (pintype "bidirectional"))
      (node (ref "IC8") (pin "H8") (pinfunction "DQ5_H8") (pintype "bidirectional"))
    )
    (net (code "50") (name "/DDR_DQ22") (class "Default")
      (node (ref "IC4") (pin "V3") (pinfunction "IO_L10P_T1_34_V3") (pintype "bidirectional"))
      (node (ref "IC8") (pin "G2") (pinfunction "DQ6_G2") (pintype "bidirectional"))
    )
    (net (code "51") (name "/DDR_DQ23") (class "Default")
      (node (ref "IC4") (pin "W3") (pinfunction "IO_L10N_T1_34_W3") (pintype "bidirectional"))
      (node (ref "IC8") (pin "H7") (pinfunction "DQ7_H7") (pintype "bidirectional"))
    )
    (net (code "52") (name "/DDR_DQ24") (class "Default")
      (node (ref "IC4") (pin "Y7") (pinfunction "IO_L5N_T0_34_Y7") (pintype "bidirectional"))
      (node (ref "IC8") (pin "D7") (pinfunction "DQ8_D7") (pintype "bidirectional"))
    )
    (net (code "53") (name "/DDR_DQ25") (class "Default")
      (node (ref "IC4") (pin "W6") (pinfunction "IO_L6P_T0_34_W6") (pintype "bidirectional"))
      (node (ref "IC8") (pin "C3") (pinfunction "DQ9_C3") (pintype "bidirectional"))
    )
    (net (code "54") (name "/DDR_DQ26") (class "Default")
      (node (ref "IC4") (pin "V6") (pinfunction "IO_L4N_T0_34_V6") (pintype "bidirectional"))
      (node (ref "IC8") (pin "C8") (pinfunction "DQ10_C8") (pintype "bidirectional"))
    )
    (net (code "55") (name "/DDR_DQ27") (class "Default")
      (node (ref "IC4") (pin "V9") (pinfunction "IO_L2P_T0_34_V9") (pintype "bidirectional"))
      (node (ref "IC8") (pin "C2") (pinfunction "DQ11_C2") (pintype "bidirectional"))
    )
    (net (code "56") (name "/DDR_DQ28") (class "Default")
      (node (ref "IC4") (pin "V8") (pinfunction "IO_L2N_T0_34_V8") (pintype "bidirectional"))
      (node (ref "IC8") (pin "A7") (pinfunction "DQ12_A7") (pintype "bidirectional"))
    )
    (net (code "57") (name "/DDR_DQ29") (class "Default")
      (node (ref "IC4") (pin "W10") (pinfunction "IO_L1P_T0_34_W10") (pintype "bidirectional"))
      (node (ref "IC8") (pin "A2") (pinfunction "DQ13_A2") (pintype "bidirectional"))
    )
    (net (code "58") (name "/DDR_DQ30") (class "Default")
      (node (ref "IC4") (pin "V7") (pinfunction "IO_L4P_T0_34_V7") (pintype "bidirectional"))
      (node (ref "IC8") (pin "B8") (pinfunction "DQ14_B8") (pintype "bidirectional"))
    )
    (net (code "59") (name "/DDR_DQ31") (class "Default")
      (node (ref "IC4") (pin "Y8") (pinfunction "IO_L5P_T0_34_Y8") (pintype "bidirectional"))
      (node (ref "IC8") (pin "A3") (pinfunction "DQ15_A3") (pintype "bidirectional"))
    )
    (net (code "60") (name "/DDR_DQS0_N") (class "Default")
      (node (ref "IC36") (pin "G3") (pinfunction "~{LDQS}_G3") (pintype "bidirectional"))
      (node (ref "IC4") (pin "AB6") (pinfunction "IO_L21N_T3_DQS_34_AB6") (pintype "bidirectional"))
    )
    (net (code "61") (name "/DDR_DQS0_P") (class "Default")
      (node (ref "IC36") (pin "F3") (pinfunction "LDQS_F3") (pintype "bidirectional"))
      (node (ref "IC4") (pin "AB7") (pinfunction "IO_L21P_T3_DQS_34_AB7") (pintype "bidirectional"))
    )
    (net (code "62") (name "/DDR_DQS1_N") (class "Default")
      (node (ref "IC36") (pin "B7") (pinfunction "~{UDQS}_B7") (pintype "bidirectional"))
      (node (ref "IC4") (pin "AB1") (pinfunction "IO_L15N_T2_DQS_34_AB1") (pintype "bidirectional"))
    )
    (net (code "63") (name "/DDR_DQS1_P") (class "Default")
      (node (ref "IC36") (pin "C7") (pinfunction "UDQS_C7") (pintype "bidirectional"))
      (node (ref "IC4") (pin "AB2") (pinfunction "IO_L15P_T2_DQS_34_AB2") (pintype "bidirectional"))
    )
    (net (code "64") (name "/DDR_DQS2_N") (class "Default")
      (node (ref "IC4") (pin "Y2") (pinfunction "IO_L9N_T1_DQS_34_Y2") (pintype "bidirectional"))
      (node (ref "IC8") (pin "G3") (pinfunction "~{LDQS}_G3") (pintype "bidirectional"))
    )
    (net (code "65") (name "/DDR_DQS2_P") (class "Default")
      (node (ref "IC4") (pin "Y3") (pinfunction "IO_L9P_T1_DQS_34_Y3") (pintype "bidirectional"))
      (node (ref "IC8") (pin "F3") (pinfunction "LDQS_F3") (pintype "bidirectional"))
    )
    (net (code "66") (name "/DDR_DQS3_N") (class "Default")
      (node (ref "IC4") (pin "W8") (pinfunction "IO_L3N_T0_DQS_34_W8") (pintype "bidirectional"))
      (node (ref "IC8") (pin "B7") (pinfunction "~{UDQS}_B7") (pintype "bidirectional"))
    )
    (net (code "67") (name "/DDR_DQS3_P") (class "Default")
      (node (ref "IC4") (pin "W9") (pinfunction "IO_L3P_T0_DQS_34_W9") (pintype "bidirectional"))
      (node (ref "IC8") (pin "C7") (pinfunction "UDQS_C7") (pintype "bidirectional"))
    )
    (net (code "68") (name "/DDR_ODT") (class "Default")
      (node (ref "IC36") (pin "K1") (pinfunction "ODT_K1") (pintype "input"))
      (node (ref "IC4") (pin "AD1") (pinfunction "IO_L2P_T0_33_AD1") (pintype "bidirectional"))
      (node (ref "IC8") (pin "K1") (pinfunction "ODT_K1") (pintype "input"))
      (node (ref "R123") (pin "1") (pinfunction "1_1") (pintype "passive"))
    )
    (net (code "69") (name "/DDR_RAS_N") (class "Default")
      (node (ref "IC36") (pin "J3") (pinfunction "~{RAS}_J3") (pintype "input"))
      (node (ref "IC4") (pin "AD3") (pinfunction "IO_L10P_T1_33_AD3") (pintype "bidirectional"))
      (node (ref "IC8") (pin "J3") (pinfunction "~{RAS}_J3") (pintype "input"))
      (node (ref "R117") (pin "1") (pinfunction "1_1") (pintype "passive"))
    )
    (net (code "70") (name "/DDR_RST_N") (class "Default")
      (node (ref "IC36") (pin "T2") (pinfunction "~{RESET}_T2") (pintype "input"))
      (node (ref "IC4") (pin "AH7") (pinfunction "IO_L17P_T2_33_AH7") (pintype "bidirectional"))
      (node (ref "IC8") (pin "T2") (pinfunction "~{RESET}_T2") (pintype "input"))
      (node (ref "R125") (pin "1") (pinfunction "1_1") (pintype "passive"))
    )
    (net (code "71") (name "/DDR_WE_N") (class "Default")
      (node (ref "IC36") (pin "L3") (pinfunction "~{WE}_L3") (pintype "input"))
      (node (ref "IC4") (pin "AF2") (pinfunction "IO_L4N_T0_33_AF2") (pintype "bidirectional"))
      (node (ref "IC8") (pin "L3") (pinfunction "~{WE}_L3") (pintype "input"))
      (node (ref "R119") (pin "1") (pinfunction "1_1") (pintype "passive"))
    )
    (net (code "72") (name "GND") (class "Default")
      (node (ref "C162") (pin "1") (pinfunction "1_1") (pintype "passive"))
      (node (ref "C163") (pin "1") (pinfunction "1_1") (pintype "passive"))
      (node (ref "C164") (pin "1") (pinfunction "1_1") (pintype "passive"))
      (node (ref "C165") (pin "1") (pinfunction "1_1") (pintype "passive"))
      (node (ref "C166") (pin "1") (pinfunction "1_1") (pintype "passive"))
      (node (ref "C167") (pin "1") (pinfunction "1_1") (pintype "passive"))
      (node (ref "C168") (pin "1") (pinfunction "1_1") (pintype "passive"))
      (node (ref "C169") (pin "1") (pinfunction "1_1") (pintype "passive"))
      (node (ref "C170") (pin "1") (pinfunction "1_1") (pintype "passive"))
      (node (ref "C171") (pin "1") (pinfunction "1_1") (pintype "passive"))
      (node (ref "C172") (pin "1") (pinfunction "1_1") (pintype "passive"))
      (node (ref "C173") (pin "1") (pinfunction "1_1") (pintype "passive"))
      (node (ref "C174") (pin "1") (pinfunction "1_1") (pintype "passive"))
      (node (ref "C175") (pin "1") (pinfunction "1_1") (pintype "passive"))
      (node (ref "C176") (pin "1") (pinfunction "1_1") (pintype "passive"))
      (node (ref "C177") (pin "1") (pinfunction "1_1") (pintype "passive"))
      (node (ref "C451") (pin "1") (pinfunction "1_1") (pintype "passive"))
      (node (ref "C452") (pin "1") (pinfunction "1_1") (pintype "passive"))
      (node (ref "C453") (pin "1") (pinfunction "1_1") (pintype "passive"))
      (node (ref "C454") (pin "1") (pinfunction "1_1") (pintype "passive"))
      (node (ref "C455") (pin "1") (pinfunction "1_1") (pintype "passive"))
      (node (ref "C456") (pin "1") (pinfunction "1_1") (pintype "passive"))
      (node (ref "C457") (pin "1") (pinfunction "1_1") (pintype "passive"))
      (node (ref "C458") (pin "1") (pinfunction "1_1") (pintype "passive"))
      (node (ref "C459") (pin "1") (pinfunction "1_1") (pintype "passive"))
      (node (ref "C460") (pin "1") (pinfunction "1_1") (pintype "passive"))
      (node (ref "C461") (pin "1") (pinfunction "1_1") (pintype "passive"))
      (node (ref "C462") (pin "1") (pinfunction "1_1") (pintype "passive"))
      (node (ref "C463") (pin "1") (pinfunction "1_1") (pintype "passive"))
      (node (ref "C464") (pin "1") (pinfunction "1_1") (pintype "passive"))
      (node (ref "C465") (pin "1") (pinfunction "1_1") (pintype "passive"))
      (node (ref "C466") (pin "1") (pinfunction "1_1") (pintype "passive"))
      (node (ref "C467") (pin "1") (pinfunction "1_1") (pintype "passive"))
      (node (ref "C468") (pin "1") (pinfunction "1_1") (pintype "passive"))
      (node (ref "C469") (pin "1") (pinfunction "1_1") (pintype "passive"))
      (node (ref "C470") (pin "1") (pinfunction "1_1") (pintype "passive"))
      (node (ref "C471") (pin "1") (pinfunction "1_1") (pintype "passive"))
      (node (ref "C472") (pin "1") (pinfunction "1_1") (pintype "passive"))
      (node (ref "C473") (pin "1") (pinfunction "1_1") (pintype "passive"))
      (node (ref "C474") (pin "1") (pinfunction "1_1") (pintype "passive"))
      (node (ref "C475") (pin "1") (pinfunction "1_1") (pintype "passive"))
      (node (ref "C476") (pin "1") (pinfunction "1_1") (pintype "passive"))
      (node (ref "C477") (pin "1") (pinfunction "1_1") (pintype "passive"))
      (node (ref "C478") (pin "1") (pinfunction "1_1") (pintype "passive"))
      (node (ref "IC36") (pin "A9") (pinfunction "VSS_A9") (pintype "power_in"))
      (node (ref "IC36") (pin "B1") (pinfunction "VSSQ_B1") (pintype "power_in"))
      (node (ref "IC36") (pin "B3") (pinfunction "VSS_B3") (pintype "power_in"))
      (node (ref "IC36") (pin "B9") (pinfunction "VSSQ_B9") (pintype "power_in"))
      (node (ref "IC36") (pin "D1") (pinfunction "VSSQ_D1") (pintype "power_in"))
      (node (ref "IC36") (pin "D8") (pinfunction "VSSQ_D8") (pintype "power_in"))
      (node (ref "IC36") (pin "E1") (pinfunction "VSS_E1") (pintype "power_in"))
      (node (ref "IC36") (pin "E2") (pinfunction "VSSQ_E2") (pintype "power_in"))
      (node (ref "IC36") (pin "E8") (pinfunction "VSSQ_E8") (pintype "power_in"))
      (node (ref "IC36") (pin "F9") (pinfunction "VSSQ_F9") (pintype "power_in"))
      (node (ref "IC36") (pin "G1") (pinfunction "VSSQ_G1") (pintype "power_in"))
      (node (ref "IC36") (pin "G8") (pinfunction "VSS_G8") (pintype "power_in"))
      (node (ref "IC36") (pin "G9") (pinfunction "VSSQ_G9") (pintype "power_in"))
      (node (ref "IC36") (pin "J2") (pinfunction "VSS_J2") (pintype "power_in"))
      (node (ref "IC36") (pin "J8") (pinfunction "VSS_J8") (pintype "power_in"))
      (node (ref "IC36") (pin "M1") (pinfunction "VSS_M1") (pintype "power_in"))
      (node (ref "IC36") (pin "M9") (pinfunction "VSS_M9") (pintype "power_in"))
      (node (ref "IC36") (pin "P1") (pinfunction "VSS_P1") (pintype "power_in"))
      (node (ref "IC36") (pin "P9") (pinfunction "VSS_P9") (pintype "power_in"))
      (node (ref "IC36") (pin "T1") (pinfunction "VSS_T1") (pintype "power_in"))
      (node (ref "IC36") (pin "T9") (pinfunction "VSS_T9") (pintype "power_in"))
      (node (ref "IC8") (pin "A9") (pinfunction "VSS_A9") (pintype "power_in"))
      (node (ref "IC8") (pin "B1") (pinfunction "VSSQ_B1") (pintype "power_in"))
      (node (ref "IC8") (pin "B3") (pinfunction "VSS_B3") (pintype "power_in"))
      (node (ref "IC8") (pin "B9") (pinfunction "VSSQ_B9") (pintype "power_in"))
      (node (ref "IC8") (pin "D1") (pinfunction "VSSQ_D1") (pintype "power_in"))
      (node (ref "IC8") (pin "D8") (pinfunction "VSSQ_D8") (pintype "power_in"))
      (node (ref "IC8") (pin "E1") (pinfunction "VSS_E1") (pintype "power_in"))
      (node (ref "IC8") (pin "E2") (pinfunction "VSSQ_E2") (pintype "power_in"))
      (node (ref "IC8") (pin "E8") (pinfunction "VSSQ_E8") (pintype "power_in"))
      (node (ref "IC8") (pin "F9") (pinfunction "VSSQ_F9") (pintype "power_in"))
      (node (ref "IC8") (pin "G1") (pinfunction "VSSQ_G1") (pintype "power_in"))
      (node (ref "IC8") (pin "G8") (pinfunction "VSS_G8") (pintype "power_in"))
      (node (ref "IC8") (pin "G9") (pinfunction "VSSQ_G9") (pintype "power_in"))
      (node (ref "IC8") (pin "J2") (pinfunction "VSS_J2") (pintype "power_in"))
      (node (ref "IC8") (pin "J8") (pinfunction "VSS_J8") (pintype "power_in"))
      (node (ref "IC8") (pin "M1") (pinfunction "VSS_M1") (pintype "power_in"))
      (node (ref "IC8") (pin "M9") (pinfunction "VSS_M9") (pintype "power_in"))
      (node (ref "IC8") (pin "P1") (pinfunction "VSS_P1") (pintype "power_in"))
      (node (ref "IC8") (pin "P9") (pinfunction "VSS_P9") (pintype "power_in"))
      (node (ref "IC8") (pin "T1") (pinfunction "VSS_T1") (pintype "power_in"))
      (node (ref "IC8") (pin "T9") (pinfunction "VSS_T9") (pintype "power_in"))
      (node (ref "IC9") (pin "11") (pinfunction "EP_11") (pintype "power_in"))
      (node (ref "IC9") (pin "4") (pinfunction "PGND_4") (pintype "power_in"))
      (node (ref "IC9") (pin "8") (pinfunction "GND_8") (pintype "power_in"))
      (node (ref "R100") (pin "1") (pinfunction "1_1") (pintype "passive"))
      (node (ref "R125") (pin "2") (pinfunction "2_2") (pintype "passive"))
      (node (ref "R129") (pin "1") (pinfunction "1_1") (pintype "passive"))
      (node (ref "R99") (pin "1") (pinfunction "1_1") (pintype "passive"))
    )
    (net (code "73") (name "Net-(IC8-ZQ)") (class "Default")
      (node (ref "IC8") (pin "L8") (pinfunction "ZQ_L8") (pintype "input"))
      (node (ref "R99") (pin "2") (pinfunction "2_2") (pintype "passive"))
    )
    (net (code "74") (name "Net-(IC9-PGOOD)") (class "Default")
      (node (ref "IC9") (pin "9") (pinfunction "PGOOD_9") (pintype "output"))
      (node (ref "R127") (pin "1") (pinfunction "1_1") (pintype "passive"))
    )
    (net (code "75") (name "Net-(IC9-REFIN)") (class "Default")
      (node (ref "C175") (pin "2") (pinfunction "2_2") (pintype "passive"))
      (node (ref "IC9") (pin "1") (pinfunction "REFIN_1") (pintype "input"))
      (node (ref "R128") (pin "2") (pinfunction "2_2") (pintype "passive"))
      (node (ref "R129") (pin "2") (pinfunction "2_2") (pintype "passive"))
    )
    (net (code "76") (name "Net-(IC36-ZQ)") (class "Default")
      (node (ref "IC36") (pin "L8") (pinfunction "ZQ_L8") (pintype "input"))
      (node (ref "R100") (pin "2") (pinfunction "2_2") (pintype "passive"))
    )
    (net (code "77") (name "P1V5") (class "Default")
      (node (ref "C170") (pin "2") (pinfunction "2_2") (pintype "passive"))
      (node (ref "C171") (pin "2") (pinfunction "2_2") (pintype "passive"))
      (node (ref "C176") (pin "2") (pinfunction "2_2") (pintype "passive"))
      (node (ref "C451") (pin "2") (pinfunction "2_2") (pintype "passive"))
      (node (ref "C452") (pin "2") (pinfunction "2_2") (pintype "passive"))
      (node (ref "C453") (pin "2") (pinfunction "2_2") (pintype "passive"))
      (node (ref "C454") (pin "2") (pinfunction "2_2") (pintype "passive"))
      (node (ref "C455") (pin "2") (pinfunction "2_2") (pintype "passive"))
      (node (ref "C456") (pin "2") (pinfunction "2_2") (pintype "passive"))
      (node (ref "C457") (pin "2") (pinfunction "2_2") (pintype "passive"))
      (node (ref "C458") (pin "2") (pinfunction "2_2") (pintype "passive"))
      (node (ref "C459") (pin "2") (pinfunction "2_2") (pintype "passive"))
      (node (ref "C460") (pin "2") (pinfunction "2_2") (pintype "passive"))
      (node (ref "C461") (pin "2") (pinfunction "2_2") (pintype "passive"))
      (node (ref "C462") (pin "2") (pinfunction "2_2") (pintype "passive"))
      (node (ref "C463") (pin "2") (pinfunction "2_2") (pintype "passive"))
      (node (ref "C464") (pin "2") (pinfunction "2_2") (pintype "passive"))
      (node (ref "C465") (pin "2") (pinfunction "2_2") (pintype "passive"))
      (node (ref "C466") (pin "2") (pinfunction "2_2") (pintype "passive"))
      (node (ref "C467") (pin "2") (pinfunction "2_2") (pintype "passive"))
      (node (ref "C468") (pin "2") (pinfunction "2_2") (pintype "passive"))
      (node (ref "C469") (pin "2") (pinfunction "2_2") (pintype "passive"))
      (node (ref "C470") (pin "2") (pinfunction "2_2") (pintype "passive"))
      (node (ref "IC36") (pin "A1") (pinfunction "VDDQ_A1") (pintype "power_in"))
      (node (ref "IC36") (pin "A8") (pinfunction "VDDQ_A8") (pintype "power_in"))
      (node (ref "IC36") (pin "B2") (pinfunction "VDD_B2") (pintype "power_in"))
      (node (ref "IC36") (pin "C1") (pinfunction "VDDQ_C1") (pintype "power_in"))
      (node (ref "IC36") (pin "C9") (pinfunction "VDDQ_C9") (pintype "power_in"))
      (node (ref "IC36") (pin "D2") (pinfunction "VDDQ_D2") (pintype "power_in"))
      (node (ref "IC36") (pin "D9") (pinfunction "VDD_D9") (pintype "power_in"))
      (node (ref "IC36") (pin "E9") (pinfunction "VDDQ_E9") (pintype "power_in"))
      (node (ref "IC36") (pin "F1") (pinfunction "VDDQ_F1") (pintype "power_in"))
      (node (ref "IC36") (pin "G7") (pinfunction "VDD_G7") (pintype "power_in"))
      (node (ref "IC36") (pin "H2") (pinfunction "VDDQ_H2") (pintype "power_in"))
      (node (ref "IC36") (pin "H9") (pinfunction "VDDQ_H9") (pintype "power_in"))
      (node (ref "IC36") (pin "K2") (pinfunction "VDD_K2") (pintype "power_in"))
      (node (ref "IC36") (pin "K8") (pinfunction "VDD_K8") (pintype "power_in"))
      (node (ref "IC36") (pin "N1") (pinfunction "VDD_N1") (pintype "power_in"))
      (node (ref "IC36") (pin "N9") (pinfunction "VDD_N9") (pintype "power_in"))
      (node (ref "IC36") (pin "R1") (pinfunction "VDD_R1") (pintype "power_in"))
      (node (ref "IC36") (pin "R9") (pinfunction "VDD_R9") (pintype "power_in"))
      (node (ref "IC8") (pin "A1") (pinfunction "VDDQ_A1") (pintype "power_in"))
      (node (ref "IC8") (pin "A8") (pinfunction "VDDQ_A8") (pintype "power_in"))
      (node (ref "IC8") (pin "B2") (pinfunction "VDD_B2") (pintype "power_in"))
      (node (ref "IC8") (pin "C1") (pinfunction "VDDQ_C1") (pintype "power_in"))
      (node (ref "IC8") (pin "C9") (pinfunction "VDDQ_C9") (pintype "power_in"))
      (node (ref "IC8") (pin "D2") (pinfunction "VDDQ_D2") (pintype "power_in"))
      (node (ref "IC8") (pin "D9") (pinfunction "VDD_D9") (pintype "power_in"))
      (node (ref "IC8") (pin "E9") (pinfunction "VDDQ_E9") (pintype "power_in"))
      (node (ref "IC8") (pin "F1") (pinfunction "VDDQ_F1") (pintype "power_in"))
      (node (ref "IC8") (pin "G7") (pinfunction "VDD_G7") (pintype "power_in"))
      (node (ref "IC8") (pin "H2") (pinfunction "VDDQ_H2") (pintype "power_in"))
      (node (ref "IC8") (pin "H9") (pinfunction "VDDQ_H9") (pintype "power_in"))
      (node (ref "IC8") (pin "K2") (pinfunction "VDD_K2") (pintype "power_in"))
      (node (ref "IC8") (pin "K8") (pinfunction "VDD_K8") (pintype "power_in"))
      (node (ref "IC8") (pin "N1") (pinfunction "VDD_N1") (pintype "power_in"))
      (node (ref "IC8") (pin "N9") (pinfunction "VDD_N9") (pintype "power_in"))
      (node (ref "IC8") (pin "R1") (pinfunction "VDD_R1") (pintype "power_in"))
      (node (ref "IC8") (pin "R9") (pinfunction "VDD_R9") (pintype "power_in"))
      (node (ref "IC9") (pin "2") (pinfunction "VLDOIN_2") (pintype "input"))
      (node (ref "R128") (pin "1") (pinfunction "1_1") (pintype "passive"))
    )
    (net (code "78") (name "P3V3") (class "Default")
      (node (ref "C172") (pin "2") (pinfunction "2_2") (pintype "passive"))
      (node (ref "IC9") (pin "10") (pinfunction "VIN_10") (pintype "input"))
      (node (ref "IC9") (pin "7") (pinfunction "EN_7") (pintype "input"))
      (node (ref "R127") (pin "2") (pinfunction "2_2") (pintype "passive"))
    )
    (net (code "79") (name "VREF_DDR3") (class "Default")
      (node (ref "C162") (pin "2") (pinfunction "2_2") (pintype "passive"))
      (node (ref "C163") (pin "2") (pinfunction "2_2") (pintype "passive"))
      (node (ref "C164") (pin "2") (pinfunction "2_2") (pintype "passive"))
      (node (ref "C165") (pin "2") (pinfunction "2_2") (pintype "passive"))
      (node (ref "C166") (pin "2") (pinfunction "2_2") (pintype "passive"))
      (node (ref "C167") (pin "2") (pinfunction "2_2") (pintype "passive"))
      (node (ref "C168") (pin "2") (pinfunction "2_2") (pintype "passive"))
      (node (ref "C169") (pin "2") (pinfunction "2_2") (pintype "passive"))
      (node (ref "C177") (pin "2") (pinfunction "2_2") (pintype "passive"))
      (node (ref "IC36") (pin "H1") (pinfunction "VREFDQ_H1") (pintype "power_in"))
      (node (ref "IC36") (pin "M8") (pinfunction "VREFCA_M8") (pintype "power_in"))
      (node (ref "IC4") (pin "AA7") (pinfunction "IO_L19N_T3_VREF_34_AA7") (pintype "bidirectional"))
      (node (ref "IC4") (pin "AH8") (pinfunction "IO_L19N_T3_VREF_33_AH8") (pintype "bidirectional"))
      (node (ref "IC4") (pin "AJ3") (pinfunction "IO_L6N_T0_VREF_33_AJ3") (pintype "bidirectional"))
      (node (ref "IC4") (pin "Y6") (pinfunction "IO_L6N_T0_VREF_34_Y6") (pintype "bidirectional"))
      (node (ref "IC8") (pin "H1") (pinfunction "VREFDQ_H1") (pintype "power_in"))
      (node (ref "IC8") (pin "M8") (pinfunction "VREFCA_M8") (pintype "power_in"))
      (node (ref "IC9") (pin "6") (pinfunction "REFOUT_6") (pintype "output"))
    )
    (net (code "80") (name "VTT_DDR3") (class "Default")
      (node (ref "C173") (pin "2") (pinfunction "2_2") (pintype "passive"))
      (node (ref "C174") (pin "2") (pinfunction "2_2") (pintype "passive"))
      (node (ref "C471") (pin "2") (pinfunction "2_2") (pintype "passive"))
      (node (ref "C472") (pin "2") (pinfunction "2_2") (pintype "passive"))
      (node (ref "C473") (pin "2") (pinfunction "2_2") (pintype "passive"))
      (node (ref "C474") (pin "2") (pinfunction "2_2") (pintype "passive"))
      (node (ref "C475") (pin "2") (pinfunction "2_2") (pintype "passive"))
      (node (ref "C476") (pin "2") (pinfunction "2_2") (pintype "passive"))
      (node (ref "C477") (pin "2") (pinfunction "2_2") (pintype "passive"))
      (node (ref "C478") (pin "2") (pinfunction "2_2") (pintype "passive"))
      (node (ref "IC9") (pin "3") (pinfunction "VO_3") (pintype "power_in"))
      (node (ref "IC9") (pin "5") (pinfunction "VOSNS_5") (pintype "input"))
      (node (ref "R101") (pin "2") (pinfunction "2_2") (pintype "passive"))
      (node (ref "R102") (pin "2") (pinfunction "2_2") (pintype "passive"))
      (node (ref "R103") (pin "2") (pinfunction "2_2") (pintype "passive"))
      (node (ref "R104") (pin "2") (pinfunction "2_2") (pintype "passive"))
      (node (ref "R105") (pin "2") (pinfunction "2_2") (pintype "passive"))
      (node (ref "R106") (pin "2") (pinfunction "2_2") (pintype "passive"))
      (node (ref "R107") (pin "2") (pinfunction "2_2") (pintype "passive"))
      (node (ref "R108") (pin "2") (pinfunction "2_2") (pintype "passive"))
      (node (ref "R109") (pin "2") (pinfunction "2_2") (pintype "passive"))
      (node (ref "R110") (pin "2") (pinfunction "2_2") (pintype "passive"))
      (node (ref "R111") (pin "2") (pinfunction "2_2") (pintype "passive"))
      (node (ref "R112") (pin "2") (pinfunction "2_2") (pintype "passive"))
      (node (ref "R113") (pin "2") (pinfunction "2_2") (pintype "passive"))
      (node (ref "R114") (pin "2") (pinfunction "2_2") (pintype "passive"))
      (node (ref "R115") (pin "2") (pinfunction "2_2") (pintype "passive"))
      (node (ref "R116") (pin "2") (pinfunction "2_2") (pintype "passive"))
      (node (ref "R117") (pin "2") (pinfunction "2_2") (pintype "passive"))
      (node (ref "R118") (pin "2") (pinfunction "2_2") (pintype "passive"))
      (node (ref "R119") (pin "2") (pinfunction "2_2") (pintype "passive"))
      (node (ref "R120") (pin "2") (pinfunction "2_2") (pintype "passive"))
      (node (ref "R121") (pin "2") (pinfunction "2_2") (pintype "passive"))
      (node (ref "R122") (pin "2") (pinfunction "2_2") (pintype "passive"))
      (node (ref "R123") (pin "2") (pinfunction "2_2") (pintype "passive"))
      (node (ref "R124") (pin "2") (pinfunction "2_2") (pintype "passive"))
      (node (ref "R126") (pin "2") (pinfunction "2_2") (pintype "passive"))
      (node (ref "R298") (pin "2") (pinfunction "2_2") (pintype "passive"))
    )
    (net (code "81") (name "unconnected-(IC4G-IO_0_33-PadAC11)") (class "Default")
      (node (ref "IC4") (pin "AC11") (pinfunction "IO_0_33_AC11") (pintype "bidirectional"))
    )
    (net (code "82") (name "unconnected-(IC4G-IO_25_33-PadAF10)") (class "Default")
      (node (ref "IC4") (pin "AF10") (pinfunction "IO_25_33_AF10") (pintype "bidirectional"))
    )
    (net (code "83") (name "unconnected-(IC4G-IO_L7P_T1_33-PadAF4)") (class "Default")
      (node (ref "IC4") (pin "AF4") (pinfunction "IO_L7P_T1_33_AF4") (pintype "bidirectional"))
    )
    (net (code "84") (name "unconnected-(IC4G-IO_L13N_T2_MRCC_33-PadAE6)") (class "Default")
      (node (ref "IC4") (pin "AE6") (pinfunction "IO_L13N_T2_MRCC_33_AE6") (pintype "bidirectional"))
    )
    (net (code "85") (name "unconnected-(IC4G-IO_L14N_T2_SRCC_33-PadAG7)") (class "Default")
      (node (ref "IC4") (pin "AG7") (pinfunction "IO_L14N_T2_SRCC_33_AG7") (pintype "bidirectional"))
    )
    (net (code "86") (name "unconnected-(IC4G-IO_L14P_T2_SRCC_33-PadAF7)") (class "Default")
      (node (ref "IC4") (pin "AF7") (pinfunction "IO_L14P_T2_SRCC_33_AF7") (pintype "bidirectional"))
    )
    (net (code "87") (name "unconnected-(IC4G-IO_L15N_T2_DQS_33-PadAD8)") (class "Default")
      (node (ref "IC4") (pin "AD8") (pinfunction "IO_L15N_T2_DQS_33_AD8") (pintype "bidirectional"))
    )
    (net (code "88") (name "unconnected-(IC4G-IO_L15P_T2_DQS_33-PadAD9)") (class "Default")
      (node (ref "IC4") (pin "AD9") (pinfunction "IO_L15P_T2_DQS_33_AD9") (pintype "bidirectional"))
    )
    (net (code "89") (name "unconnected-(IC4G-IO_L16P_T2_33-PadAE8)") (class "Default")
      (node (ref "IC4") (pin "AE8") (pinfunction "IO_L16P_T2_33_AE8") (pintype "bidirectional"))
    )
    (net (code "90") (name "unconnected-(IC4G-IO_L18P_T2_33-PadAF9)") (class "Default")
      (node (ref "IC4") (pin "AF9") (pinfunction "IO_L18P_T2_33_AF9") (pintype "bidirectional"))
    )
    (net (code "91") (name "unconnected-(IC4G-IO_L19P_T3_33-PadAH9)") (class "Default")
      (node (ref "IC4") (pin "AH9") (pinfunction "IO_L19P_T3_33_AH9") (pintype "bidirectional"))
    )
    (net (code "92") (name "unconnected-(IC4G-IO_L20N_T3_33-PadAG12)") (class "Default")
      (node (ref "IC4") (pin "AG12") (pinfunction "IO_L20N_T3_33_AG12") (pintype "bidirectional"))
    )
    (net (code "93") (name "unconnected-(IC4G-IO_L20P_T3_33-PadAF12)") (class "Default")
      (node (ref "IC4") (pin "AF12") (pinfunction "IO_L20P_T3_33_AF12") (pintype "bidirectional"))
    )
    (net (code "94") (name "unconnected-(IC4G-IO_L21N_T3_DQS_33-PadAG9)") (class "Default")
      (node (ref "IC4") (pin "AG9") (pinfunction "IO_L21N_T3_DQS_33_AG9") (pintype "bidirectional"))
    )
    (net (code "95") (name "unconnected-(IC4G-IO_L21P_T3_DQS_33-PadAG10)") (class "Default")
      (node (ref "IC4") (pin "AG10") (pinfunction "IO_L21P_T3_DQS_33_AG10") (pintype "bidirectional"))
    )
    (net (code "96") (name "unconnected-(IC4G-IO_L22N_T3_33-PadAE11)") (class "Default")
      (node (ref "IC4") (pin "AE11") (pinfunction "IO_L22N_T3_33_AE11") (pintype "bidirectional"))
    )
    (net (code "97") (name "unconnected-(IC4G-IO_L22P_T3_33-PadAD11)") (class "Default")
      (node (ref "IC4") (pin "AD11") (pinfunction "IO_L22P_T3_33_AD11") (pintype "bidirectional"))
    )
    (net (code "98") (name "unconnected-(IC4G-IO_L23N_T3_33-PadAH11)") (class "Default")
      (node (ref "IC4") (pin "AH11") (pinfunction "IO_L23N_T3_33_AH11") (pintype "bidirectional"))
    )
    (net (code "99") (name "unconnected-(IC4G-IO_L23P_T3_33-PadAG11)") (class "Default")
      (node (ref "IC4") (pin "AG11") (pinfunction "IO_L23P_T3_33_AG11") (pintype "bidirectional"))
    )
    (net (code "100") (name "unconnected-(IC4G-IO_L24N_T3_33-PadAE10)") (class "Default")
      (node (ref "IC4") (pin "AE10") (pinfunction "IO_L24N_T3_33_AE10") (pintype "bidirectional"))
    )
    (net (code "101") (name "unconnected-(IC4G-IO_L24P_T3_33-PadAD10)") (class "Default")
      (node (ref "IC4") (pin "AD10") (pinfunction "IO_L24P_T3_33_AD10") (pintype "bidirectional"))
    )
    (net (code "102") (name "unconnected-(IC4H-IO_0_34-PadY11)") (class "Default")
      (node (ref "IC4") (pin "Y11") (pinfunction "IO_0_34_Y11") (pintype "bidirectional"))
    )
    (net (code "103") (name "unconnected-(IC4H-IO_25_34-PadAB11)") (class "Default")
      (node (ref "IC4") (pin "AB11") (pinfunction "IO_25_34_AB11") (pintype "bidirectional"))
    )
    (net (code "104") (name "unconnected-(IC4H-IO_L12P_T1_MRCC_34-PadW5)") (class "Default")
      (node (ref "IC4") (pin "W5") (pinfunction "IO_L12P_T1_MRCC_34_W5") (pintype "bidirectional"))
    )
    (net (code "105") (name "unconnected-(IC4H-IO_L13N_T2_MRCC_34-PadAA4)") (class "Default")
      (node (ref "IC4") (pin "AA4") (pinfunction "IO_L13N_T2_MRCC_34_AA4") (pintype "bidirectional"))
    )
    (net (code "106") (name "unconnected-(IC8-NC-PadJ1)") (class "Default")
      (node (ref "IC8") (pin "J1") (pinfunction "NC_J1") (pintype "passive+no_connect"))
    )
    (net (code "107") (name "unconnected-(IC8-NC-PadJ9)") (class "Default")
      (node (ref "IC8") (pin "J9") (pinfunction "NC_J9") (pintype "passive+no_connect"))
    )
    (net (code "108") (name "unconnected-(IC8-NC-PadL1)") (class "Default")
      (node (ref "IC8") (pin "L1") (pinfunction "NC_L1") (pintype "passive+no_connect"))
    )
    (net (code "109") (name "unconnected-(IC8-NC-PadL9)") (class "Default")
      (node (ref "IC8") (pin "L9") (pinfunction "NC_L9") (pintype "passive+no_connect"))
    )
    (net (code "110") (name "unconnected-(IC8-NC-PadM7)") (class "Default")
      (node (ref "IC8") (pin "M7") (pinfunction "NC_M7") (pintype "passive+no_connect"))
    )
    (net (code "111") (name "unconnected-(IC36-NC-PadJ1)") (class "Default")
      (node (ref "IC36") (pin "J1") (pinfunction "NC_J1") (pintype "passive+no_connect"))
    )
    (net (code "112") (name "unconnected-(IC36-NC-PadJ9)") (class "Default")
      (node (ref "IC36") (pin "J9") (pinfunction "NC_J9") (pintype "passive+no_connect"))
    )
    (net (code "113") (name "unconnected-(IC36-NC-PadL1)") (class "Default")
      (node (ref "IC36") (pin "L1") (pinfunction "NC_L1") (pintype "passive+no_connect"))
    )
    (net (code "114") (name "unconnected-(IC36-NC-PadL9)") (class "Default")
      (node (ref "IC36") (pin "L9") (pinfunction "NC_L9") (pintype "passive+no_connect"))
    )
    (net (code "115") (name "unconnected-(IC36-NC-PadM7)") (class "Default")
      (node (ref "IC36") (pin "M7") (pinfunction "NC_M7") (pintype "passive+no_connect"))
    )
  )
)
